# ETH_SWITCH.net
KiCad netlist of a schematic drawn in Altium Designer
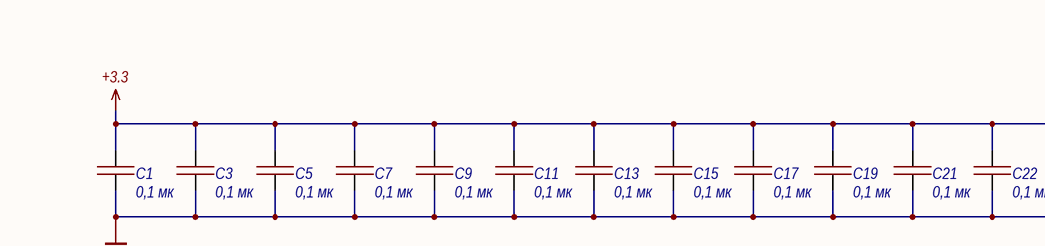
[diagram p0: ETH_SWITCH.SchDoc, top left]
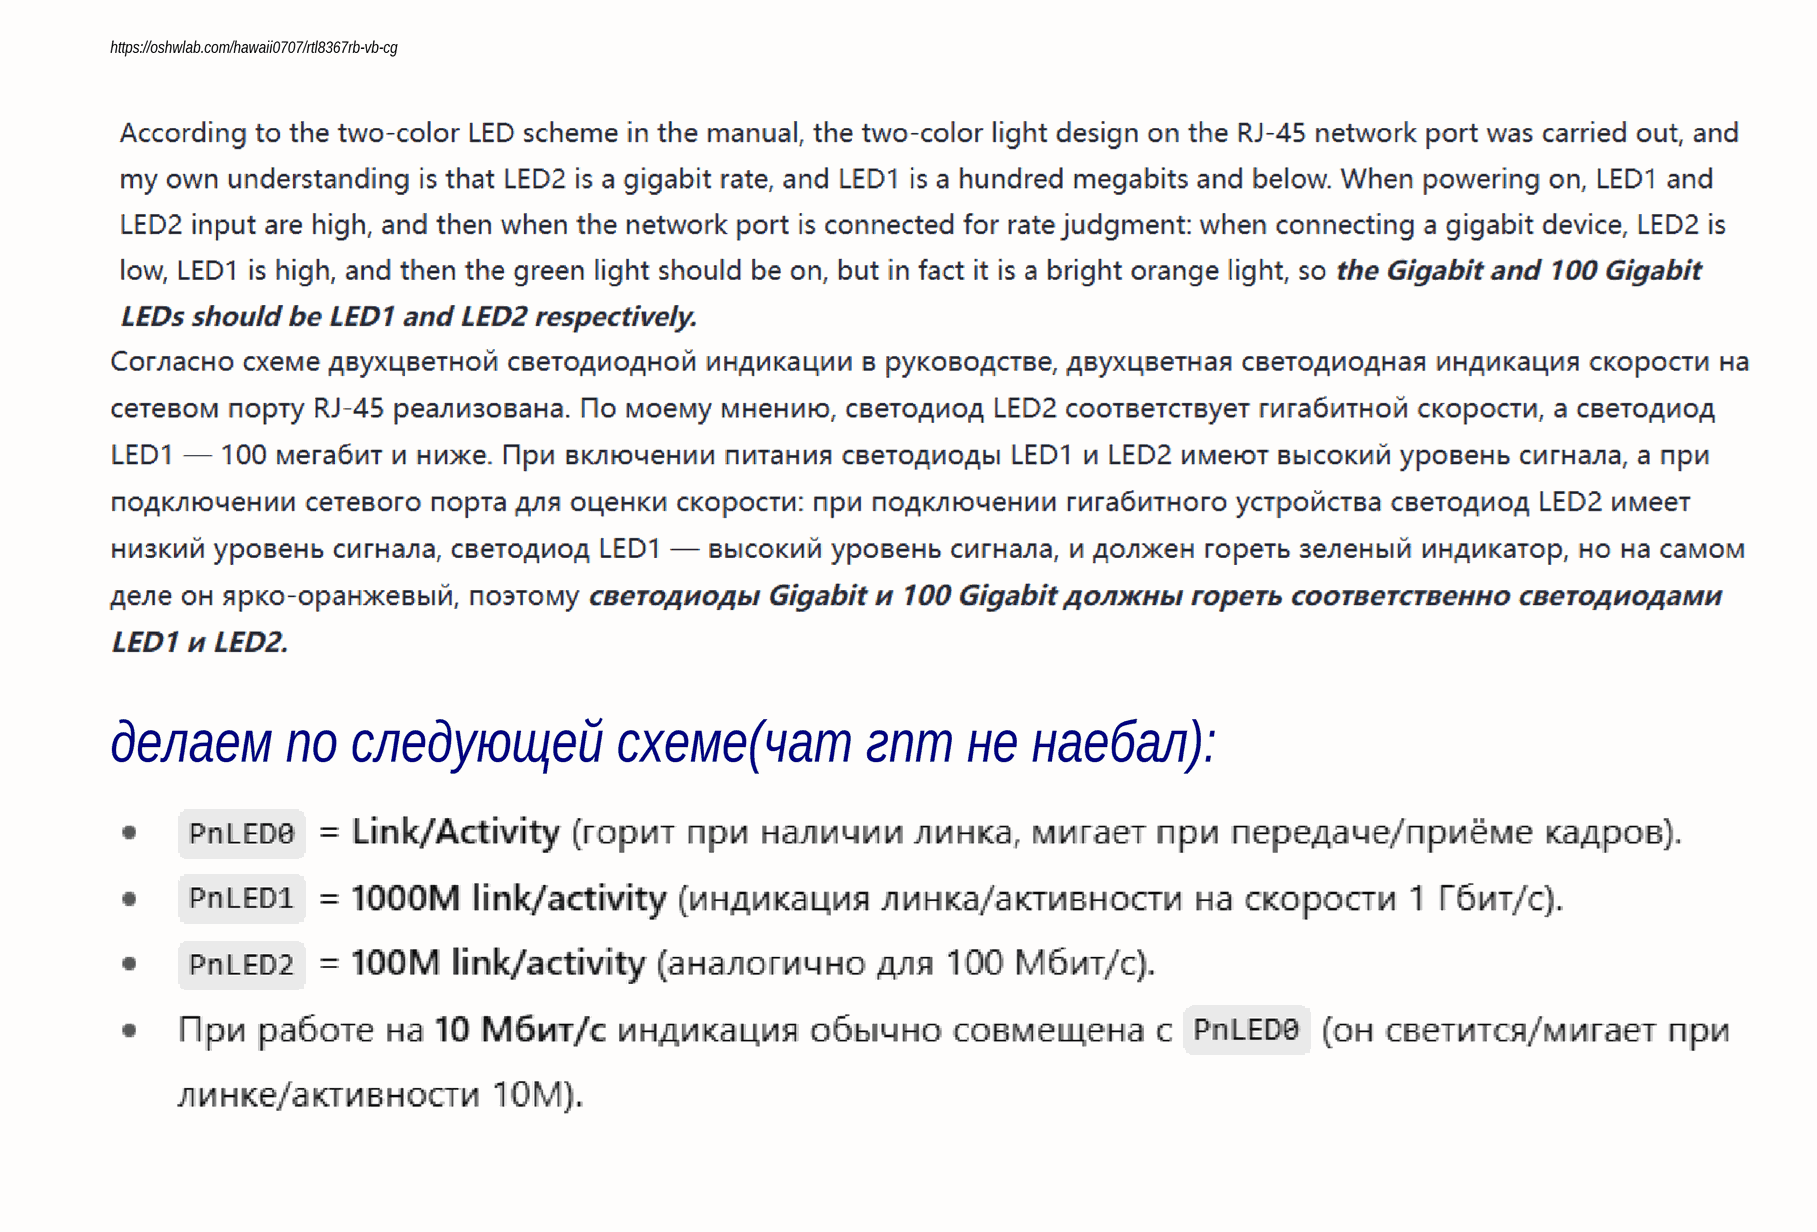
[diagram p1: ETH_SWITCH.SchDoc, top right]
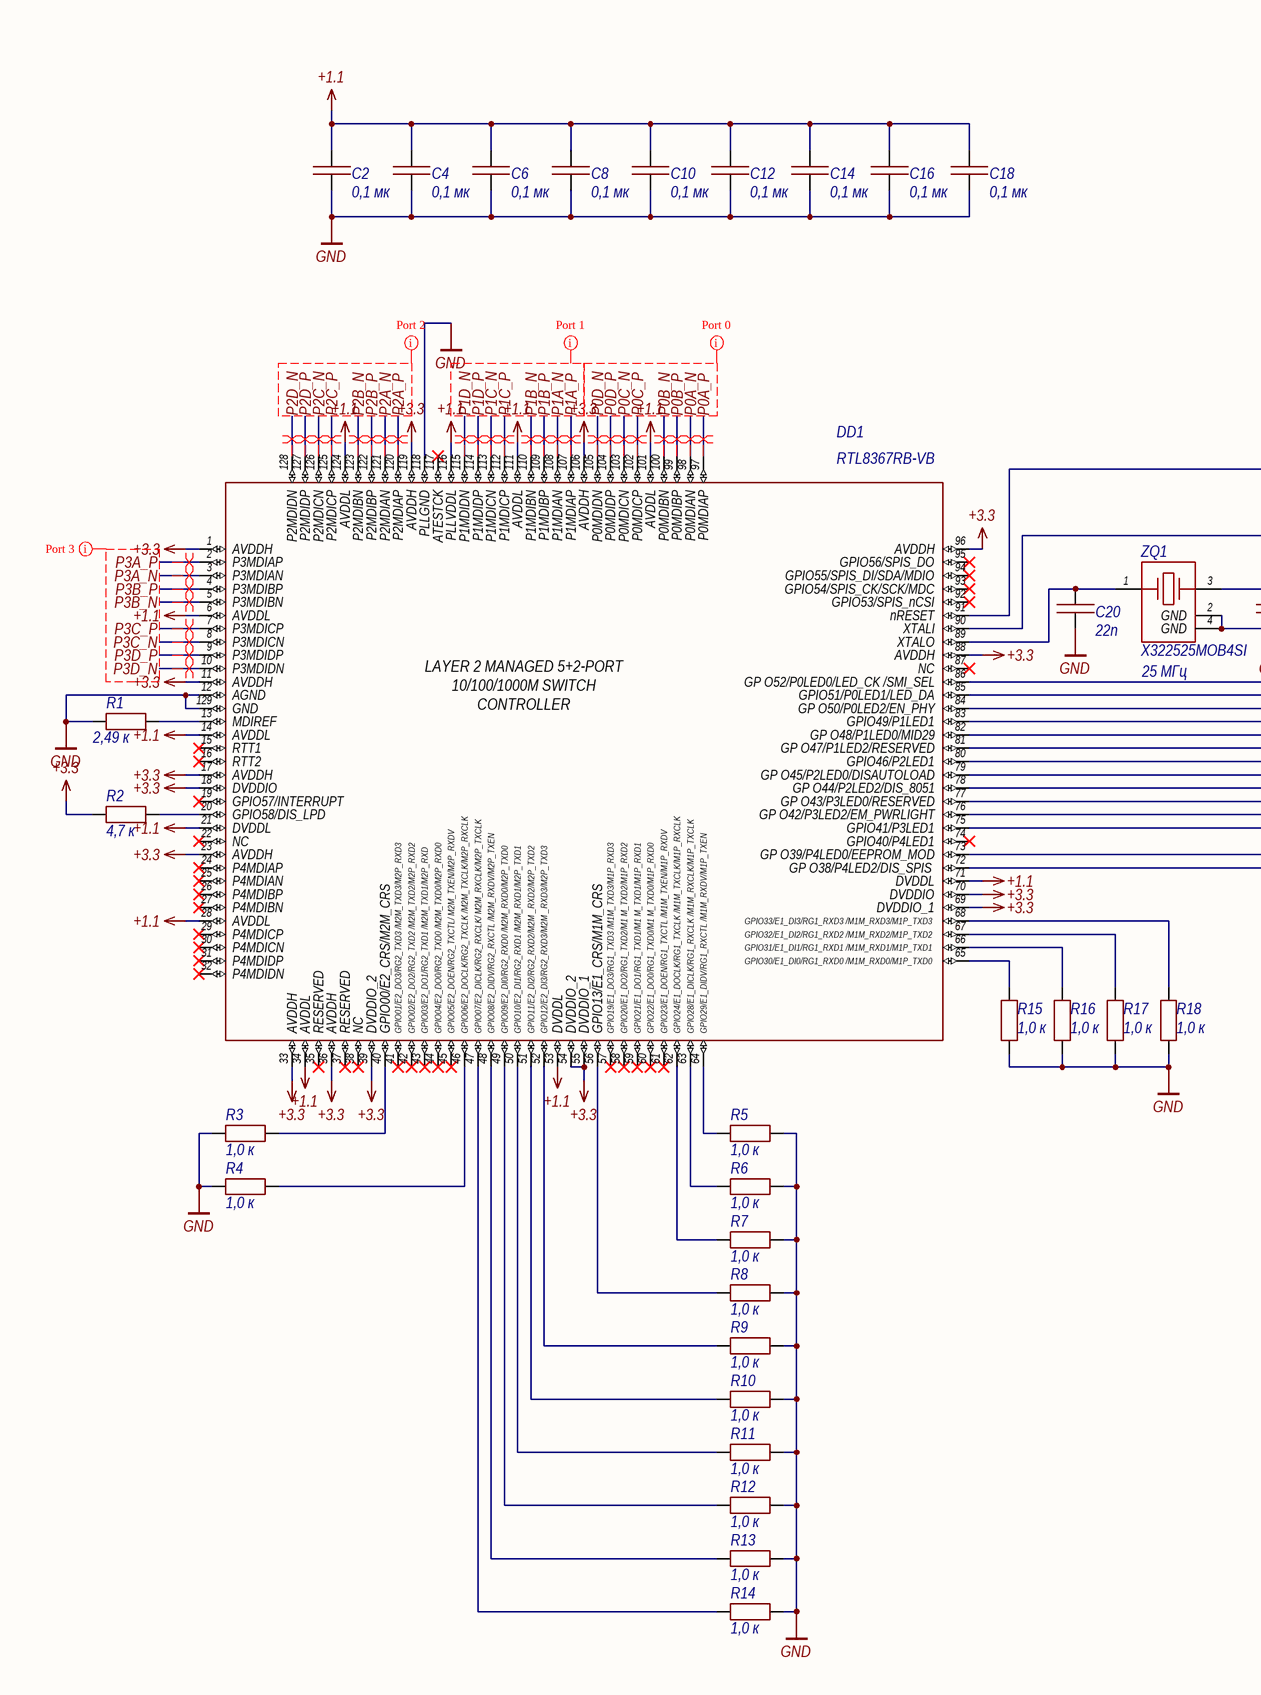
[diagram p2: ETH_SWITCH.SchDoc, bottom left]
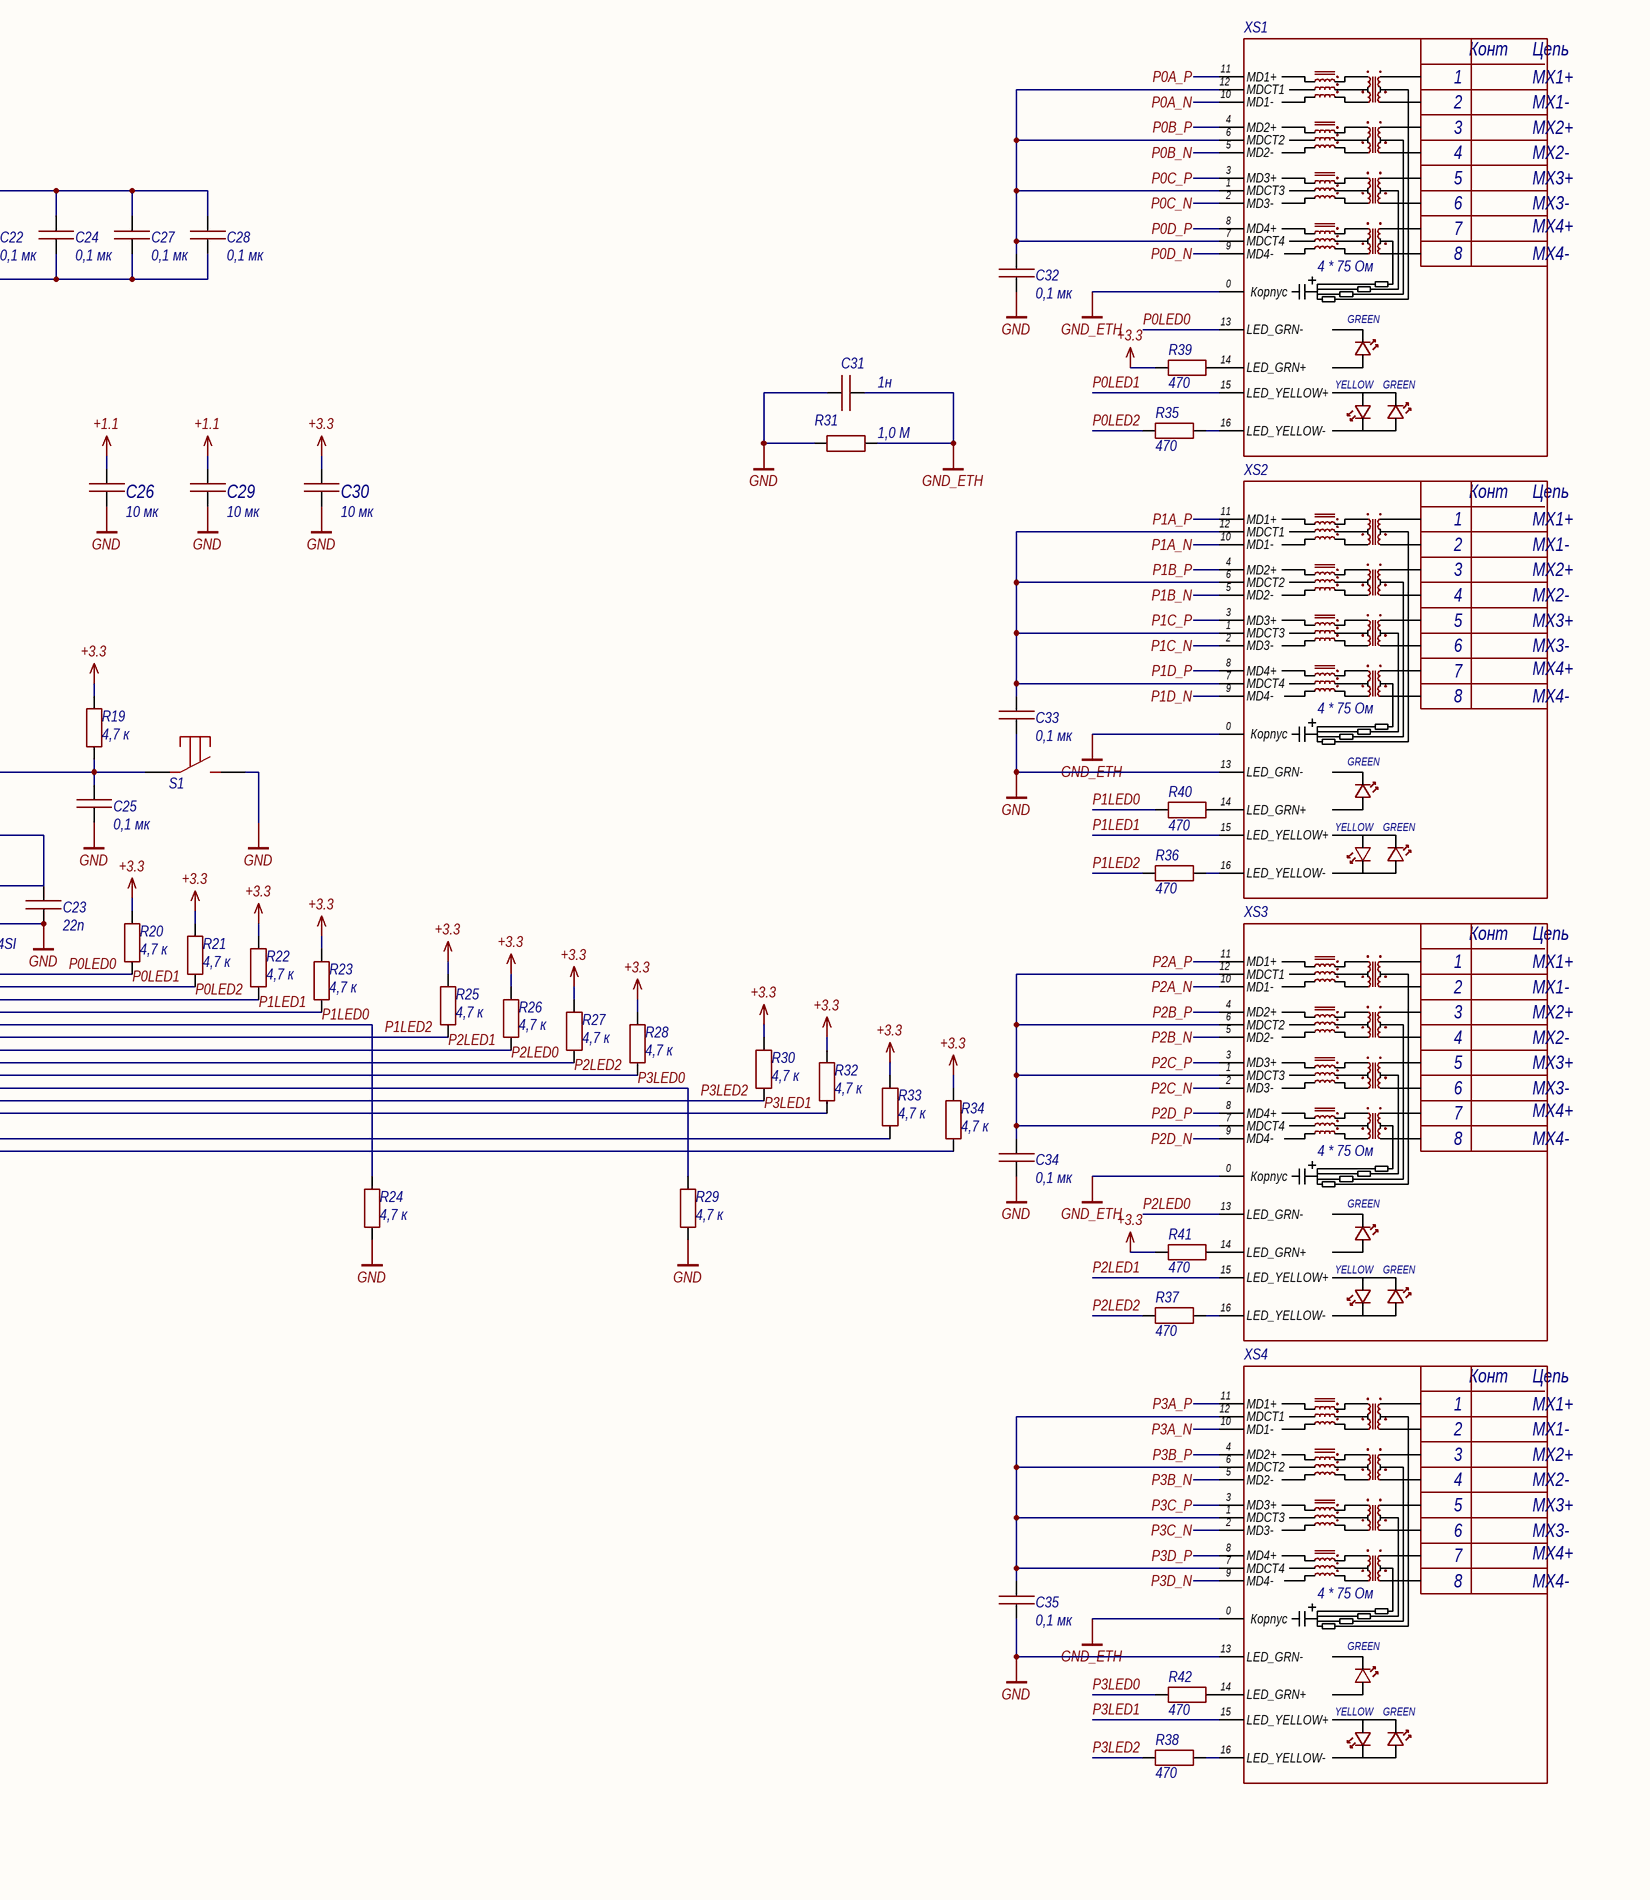
[diagram p3: ETH_SWITCH.SchDoc, bottom right]

(export (version "E")
  (design (tool "Eeschema 10.0.6"))
  (components
    (comp (ref "C1")
      (value "0,1 мк")
      (footprint "0402C")
      (description "Конденсатор 0402C ёмкостью 0,1 мк 10%, 16 В, X7R")
      (fields
        (field (name "PART NUMBER") "Capacitor_0,1u_10_16V_X7R_0603C")
        (field (name "TOLERANCE") "10%")
        (field (name "АВТОР") "rreali")
      )
      (libsource (lib "Hydrolib") (part "Capacitor"))
    )
    (comp (ref "C2")
      (value "0,1 мк")
      (footprint "0402C")
      (description "Конденсатор 0402C ёмкостью 0,1 мк 10%, 16 В, X7R")
      (fields
        (field (name "PART NUMBER") "Capacitor_0,1u_10_16V_X7R_0603C")
        (field (name "TOLERANCE") "10%")
        (field (name "АВТОР") "rreali")
      )
      (libsource (lib "Hydrolib") (part "Capacitor"))
    )
    (comp (ref "C3")
      (value "0,1 мк")
      (footprint "0402C")
      (description "Конденсатор 0402C ёмкостью 0,1 мк 10%, 16 В, X7R")
      (fields
        (field (name "PART NUMBER") "Capacitor_0,1u_10_16V_X7R_0603C")
        (field (name "TOLERANCE") "10%")
        (field (name "АВТОР") "rreali")
      )
      (libsource (lib "Hydrolib") (part "Capacitor"))
    )
    (comp (ref "C4")
      (value "0,1 мк")
      (footprint "0402C")
      (description "Конденсатор 0402C ёмкостью 0,1 мк 10%, 16 В, X7R")
      (fields
        (field (name "PART NUMBER") "Capacitor_0,1u_10_16V_X7R_0603C")
        (field (name "TOLERANCE") "10%")
        (field (name "АВТОР") "rreali")
      )
      (libsource (lib "Hydrolib") (part "Capacitor"))
    )
    (comp (ref "C5")
      (value "0,1 мк")
      (footprint "0402C")
      (description "Конденсатор 0402C ёмкостью 0,1 мк 10%, 16 В, X7R")
      (fields
        (field (name "PART NUMBER") "Capacitor_0,1u_10_16V_X7R_0603C")
        (field (name "TOLERANCE") "10%")
        (field (name "АВТОР") "rreali")
      )
      (libsource (lib "Hydrolib") (part "Capacitor"))
    )
    (comp (ref "C6")
      (value "0,1 мк")
      (footprint "0402C")
      (description "Конденсатор 0402C ёмкостью 0,1 мк 10%, 16 В, X7R")
      (fields
        (field (name "PART NUMBER") "Capacitor_0,1u_10_16V_X7R_0603C")
        (field (name "TOLERANCE") "10%")
        (field (name "АВТОР") "rreali")
      )
      (libsource (lib "Hydrolib") (part "Capacitor"))
    )
    (comp (ref "C7")
      (value "0,1 мк")
      (footprint "0402C")
      (description "Конденсатор 0402C ёмкостью 0,1 мк 10%, 16 В, X7R")
      (fields
        (field (name "PART NUMBER") "Capacitor_0,1u_10_16V_X7R_0603C")
        (field (name "TOLERANCE") "10%")
        (field (name "АВТОР") "rreali")
      )
      (libsource (lib "Hydrolib") (part "Capacitor"))
    )
    (comp (ref "C8")
      (value "0,1 мк")
      (footprint "0402C")
      (description "Конденсатор 0402C ёмкостью 0,1 мк 10%, 16 В, X7R")
      (fields
        (field (name "PART NUMBER") "Capacitor_0,1u_10_16V_X7R_0603C")
        (field (name "TOLERANCE") "10%")
        (field (name "АВТОР") "rreali")
      )
      (libsource (lib "Hydrolib") (part "Capacitor"))
    )
    (comp (ref "C9")
      (value "0,1 мк")
      (footprint "0402C")
      (description "Конденсатор 0402C ёмкостью 0,1 мк 10%, 16 В, X7R")
      (fields
        (field (name "PART NUMBER") "Capacitor_0,1u_10_16V_X7R_0603C")
        (field (name "TOLERANCE") "10%")
        (field (name "АВТОР") "rreali")
      )
      (libsource (lib "Hydrolib") (part "Capacitor"))
    )
    (comp (ref "C10")
      (value "0,1 мк")
      (footprint "0402C")
      (description "Конденсатор 0402C ёмкостью 0,1 мк 10%, 16 В, X7R")
      (fields
        (field (name "PART NUMBER") "Capacitor_0,1u_10_16V_X7R_0603C")
        (field (name "TOLERANCE") "10%")
        (field (name "АВТОР") "rreali")
      )
      (libsource (lib "Hydrolib") (part "Capacitor"))
    )
    (comp (ref "C11")
      (value "0,1 мк")
      (footprint "0402C")
      (description "Конденсатор 0402C ёмкостью 0,1 мк 10%, 16 В, X7R")
      (fields
        (field (name "PART NUMBER") "Capacitor_0,1u_10_16V_X7R_0603C")
        (field (name "TOLERANCE") "10%")
        (field (name "АВТОР") "rreali")
      )
      (libsource (lib "Hydrolib") (part "Capacitor"))
    )
    (comp (ref "C12")
      (value "0,1 мк")
      (footprint "0402C")
      (description "Конденсатор 0402C ёмкостью 0,1 мк 10%, 16 В, X7R")
      (fields
        (field (name "PART NUMBER") "Capacitor_0,1u_10_16V_X7R_0603C")
        (field (name "TOLERANCE") "10%")
        (field (name "АВТОР") "rreali")
      )
      (libsource (lib "Hydrolib") (part "Capacitor"))
    )
    (comp (ref "C13")
      (value "0,1 мк")
      (footprint "0402C")
      (description "Конденсатор 0402C ёмкостью 0,1 мк 10%, 16 В, X7R")
      (fields
        (field (name "PART NUMBER") "Capacitor_0,1u_10_16V_X7R_0603C")
        (field (name "TOLERANCE") "10%")
        (field (name "АВТОР") "rreali")
      )
      (libsource (lib "Hydrolib") (part "Capacitor"))
    )
    (comp (ref "C14")
      (value "0,1 мк")
      (footprint "0402C")
      (description "Конденсатор 0402C ёмкостью 0,1 мк 10%, 16 В, X7R")
      (fields
        (field (name "PART NUMBER") "Capacitor_0,1u_10_16V_X7R_0603C")
        (field (name "TOLERANCE") "10%")
        (field (name "АВТОР") "rreali")
      )
      (libsource (lib "Hydrolib") (part "Capacitor"))
    )
    (comp (ref "C15")
      (value "0,1 мк")
      (footprint "0402C")
      (description "Конденсатор 0402C ёмкостью 0,1 мк 10%, 16 В, X7R")
      (fields
        (field (name "PART NUMBER") "Capacitor_0,1u_10_16V_X7R_0603C")
        (field (name "TOLERANCE") "10%")
        (field (name "АВТОР") "rreali")
      )
      (libsource (lib "Hydrolib") (part "Capacitor"))
    )
    (comp (ref "C16")
      (value "0,1 мк")
      (footprint "0402C")
      (description "Конденсатор 0402C ёмкостью 0,1 мк 10%, 16 В, X7R")
      (fields
        (field (name "PART NUMBER") "Capacitor_0,1u_10_16V_X7R_0603C")
        (field (name "TOLERANCE") "10%")
        (field (name "АВТОР") "rreali")
      )
      (libsource (lib "Hydrolib") (part "Capacitor"))
    )
    (comp (ref "C17")
      (value "0,1 мк")
      (footprint "0402C")
      (description "Конденсатор 0402C ёмкостью 0,1 мк 10%, 16 В, X7R")
      (fields
        (field (name "PART NUMBER") "Capacitor_0,1u_10_16V_X7R_0603C")
        (field (name "TOLERANCE") "10%")
        (field (name "АВТОР") "rreali")
      )
      (libsource (lib "Hydrolib") (part "Capacitor"))
    )
    (comp (ref "C18")
      (value "0,1 мк")
      (footprint "0402C")
      (description "Конденсатор 0402C ёмкостью 0,1 мк 10%, 16 В, X7R")
      (fields
        (field (name "PART NUMBER") "Capacitor_0,1u_10_16V_X7R_0603C")
        (field (name "TOLERANCE") "10%")
        (field (name "АВТОР") "rreali")
      )
      (libsource (lib "Hydrolib") (part "Capacitor"))
    )
    (comp (ref "C19")
      (value "0,1 мк")
      (footprint "0402C")
      (description "Конденсатор 0402C ёмкостью 0,1 мк 10%, 16 В, X7R")
      (fields
        (field (name "PART NUMBER") "Capacitor_0,1u_10_16V_X7R_0603C")
        (field (name "TOLERANCE") "10%")
        (field (name "АВТОР") "rreali")
      )
      (libsource (lib "Hydrolib") (part "Capacitor"))
    )
    (comp (ref "C20")
      (value "22п")
      (footprint "0603C")
      (description "Конденсатор 0603C ёмкостью 22п 5%, 50 В, NP0")
      (fields (field (name "PART NUMBER") "GRM1885C1H220J") (field (name "TOLERANCE") "5%"))
      (libsource (lib "Hydrolib") (part "Capacitor"))
    )
    (comp (ref "C21")
      (value "0,1 мк")
      (footprint "0402C")
      (description "Конденсатор 0402C ёмкостью 0,1 мк 10%, 16 В, X7R")
      (fields
        (field (name "PART NUMBER") "Capacitor_0,1u_10_16V_X7R_0603C")
        (field (name "TOLERANCE") "10%")
        (field (name "АВТОР") "rreali")
      )
      (libsource (lib "Hydrolib") (part "Capacitor"))
    )
    (comp (ref "C22")
      (value "0,1 мк")
      (footprint "0402C")
      (description "Конденсатор 0402C ёмкостью 0,1 мк 10%, 16 В, X7R")
      (fields
        (field (name "PART NUMBER") "Capacitor_0,1u_10_16V_X7R_0603C")
        (field (name "TOLERANCE") "10%")
        (field (name "АВТОР") "rreali")
      )
      (libsource (lib "Hydrolib") (part "Capacitor"))
    )
    (comp (ref "C23")
      (value "22п")
      (footprint "0603C")
      (description "Конденсатор 0603C ёмкостью 22п 5%, 50 В, NP0")
      (fields (field (name "PART NUMBER") "GRM1885C1H220J") (field (name "TOLERANCE") "5%"))
      (libsource (lib "Hydrolib") (part "Capacitor"))
    )
    (comp (ref "C24")
      (value "0,1 мк")
      (footprint "0402C")
      (description "Конденсатор 0402C ёмкостью 0,1 мк 10%, 16 В, X7R")
      (fields
        (field (name "PART NUMBER") "Capacitor_0,1u_10_16V_X7R_0603C")
        (field (name "TOLERANCE") "10%")
        (field (name "АВТОР") "rreali")
      )
      (libsource (lib "Hydrolib") (part "Capacitor"))
    )
    (comp (ref "C25")
      (value "0,1 мк")
      (footprint "0603C")
      (description "Конденсатор 0603C ёмкостью 0,1 мк 10%, 50 В, X7R")
      (fields (field (name "PART NUMBER") "Capacitor_0,1u_10_50V_X7R_0603C") (field (name "TOLERANCE") "10%"))
      (libsource (lib "Hydrolib") (part "Capacitor"))
    )
    (comp (ref "C26")
      (value "10 мк")
      (footprint "1210C")
      (description "Конденсатор")
      (fields (field (name "PART NUMBER") "Capacitor_10u_10_35V_X7R_1210C") (field (name "TOLERANCE") "0,1"))
      (libsource (lib "Hydrolib") (part "Capacitor"))
    )
    (comp (ref "C27")
      (value "0,1 мк")
      (footprint "0402C")
      (description "Конденсатор 0402C ёмкостью 0,1 мк 10%, 16 В, X7R")
      (fields
        (field (name "PART NUMBER") "Capacitor_0,1u_10_16V_X7R_0603C")
        (field (name "TOLERANCE") "10%")
        (field (name "АВТОР") "rreali")
      )
      (libsource (lib "Hydrolib") (part "Capacitor"))
    )
    (comp (ref "C28")
      (value "0,1 мк")
      (footprint "0402C")
      (description "Конденсатор 0402C ёмкостью 0,1 мк 10%, 16 В, X7R")
      (fields
        (field (name "PART NUMBER") "Capacitor_0,1u_10_16V_X7R_0603C")
        (field (name "TOLERANCE") "10%")
        (field (name "АВТОР") "rreali")
      )
      (libsource (lib "Hydrolib") (part "Capacitor"))
    )
    (comp (ref "C29")
      (value "10 мк")
      (footprint "1210C")
      (description "Конденсатор")
      (fields (field (name "PART NUMBER") "Capacitor_10u_10_35V_X7R_1210C") (field (name "TOLERANCE") "0,1"))
      (libsource (lib "Hydrolib") (part "Capacitor"))
    )
    (comp (ref "C30")
      (value "10 мк")
      (footprint "1210C")
      (description "Конденсатор")
      (fields (field (name "PART NUMBER") "Capacitor_10u_10_35V_X7R_1210C") (field (name "TOLERANCE") "0,1"))
      (libsource (lib "Hydrolib") (part "Capacitor"))
    )
    (comp (ref "C31")
      (value "1н")
      (footprint "1210C")
      (description "Конденсатор 1210C ёмкостью 1н 10%, 1000 В, X7R")
      (fields (field (name "PART NUMBER") "Capacitor_1n_10_1000V_X7R_1206C") (field (name "TOLERANCE") "10%"))
      (libsource (lib "Hydrolib") (part "Capacitor"))
    )
    (comp (ref "C32")
      (value "0,1 мк")
      (footprint "0603C")
      (description "Конденсатор 0603C ёмкостью 0,1 мк 10%, 50 В, X7R")
      (fields (field (name "PART NUMBER") "Capacitor_0,1u_10_50V_X7R_0603C") (field (name "TOLERANCE") "10%"))
      (libsource (lib "Hydrolib") (part "Capacitor"))
    )
    (comp (ref "C33")
      (value "0,1 мк")
      (footprint "0603C")
      (description "Конденсатор 0603C ёмкостью 0,1 мк 10%, 50 В, X7R")
      (fields (field (name "PART NUMBER") "Capacitor_0,1u_10_50V_X7R_0603C") (field (name "TOLERANCE") "10%"))
      (libsource (lib "Hydrolib") (part "Capacitor"))
    )
    (comp (ref "C34")
      (value "0,1 мк")
      (footprint "0603C")
      (description "Конденсатор 0603C ёмкостью 0,1 мк 10%, 50 В, X7R")
      (fields (field (name "PART NUMBER") "Capacitor_0,1u_10_50V_X7R_0603C") (field (name "TOLERANCE") "10%"))
      (libsource (lib "Hydrolib") (part "Capacitor"))
    )
    (comp (ref "C35")
      (value "0,1 мк")
      (footprint "0603C")
      (description "Конденсатор 0603C ёмкостью 0,1 мк 10%, 50 В, X7R")
      (fields (field (name "PART NUMBER") "Capacitor_0,1u_10_50V_X7R_0603C") (field (name "TOLERANCE") "10%"))
      (libsource (lib "Hydrolib") (part "Capacitor"))
    )
    (comp (ref "DD1")
      (value "RTL8367RB-VB")
      (footprint "LQFP128_14x14_exposed_pad")
      (description "Управляемый коммутатор второго уровня на 5+2 порта 10/100/1000M")
      (fields (field (name "MF") "Realtek") (field (name "MP") "RTL8367RB"))
      (libsource (lib "Hydrolib") (part "RTL8367RB-VB"))
    )
    (comp (ref "R1")
      (value "2,49 к")
      (footprint "0603R")
      (description "0.1Вт 0603 2.49 кОм, 1%, Чип резистор")
      (fields (field (name "PART NUMBER") "RC0603FR-072K49L") (field (name "TOLERANCE") "1%"))
      (libsource (lib "") (part "Resistor_2"))
    )
    (comp (ref "R2")
      (value "4,7 к")
      (footprint "0402R")
      (description "Резистор номиналом 4,7 кОм 1%")
      (fields
        (field (name "PART NUMBER") "Resistor_4.7k_1_0402")
        (field (name "TOLERANCE") "1%")
        (field (name "АВТОР") "rreali")
      )
      (libsource (lib "") (part "Resistor_2"))
    )
    (comp (ref "R3")
      (value "1,0 к")
      (footprint "0402R")
      (description "Резистор номиналом 1,0 кОм 1%")
      (fields
        (field (name "PART NUMBER") "Resistor_1.0k_1_0402")
        (field (name "TOLERANCE") "1%")
        (field (name "АВТОР") "rreali")
      )
      (libsource (lib "") (part "Resistor_1"))
    )
    (comp (ref "R4")
      (value "1,0 к")
      (footprint "0402R")
      (description "Резистор номиналом 1,0 кОм 1%")
      (fields
        (field (name "PART NUMBER") "Resistor_1.0k_1_0402")
        (field (name "TOLERANCE") "1%")
        (field (name "АВТОР") "rreali")
      )
      (libsource (lib "") (part "Resistor_1"))
    )
    (comp (ref "R5")
      (value "1,0 к")
      (footprint "0402R")
      (description "Резистор номиналом 1,0 кОм 1%")
      (fields
        (field (name "PART NUMBER") "Resistor_1.0k_1_0402")
        (field (name "TOLERANCE") "1%")
        (field (name "АВТОР") "rreali")
      )
      (libsource (lib "") (part "Resistor_1"))
    )
    (comp (ref "R6")
      (value "1,0 к")
      (footprint "0402R")
      (description "Резистор номиналом 1,0 кОм 1%")
      (fields
        (field (name "PART NUMBER") "Resistor_1.0k_1_0402")
        (field (name "TOLERANCE") "1%")
        (field (name "АВТОР") "rreali")
      )
      (libsource (lib "") (part "Resistor_1"))
    )
    (comp (ref "R7")
      (value "1,0 к")
      (footprint "0402R")
      (description "Резистор номиналом 1,0 кОм 1%")
      (fields
        (field (name "PART NUMBER") "Resistor_1.0k_1_0402")
        (field (name "TOLERANCE") "1%")
        (field (name "АВТОР") "rreali")
      )
      (libsource (lib "") (part "Resistor_1"))
    )
    (comp (ref "R8")
      (value "1,0 к")
      (footprint "0402R")
      (description "Резистор номиналом 1,0 кОм 1%")
      (fields
        (field (name "PART NUMBER") "Resistor_1.0k_1_0402")
        (field (name "TOLERANCE") "1%")
        (field (name "АВТОР") "rreali")
      )
      (libsource (lib "") (part "Resistor_1"))
    )
    (comp (ref "R9")
      (value "1,0 к")
      (footprint "0402R")
      (description "Резистор номиналом 1,0 кОм 1%")
      (fields
        (field (name "PART NUMBER") "Resistor_1.0k_1_0402")
        (field (name "TOLERANCE") "1%")
        (field (name "АВТОР") "rreali")
      )
      (libsource (lib "") (part "Resistor_1"))
    )
    (comp (ref "R10")
      (value "1,0 к")
      (footprint "0402R")
      (description "Резистор номиналом 1,0 кОм 1%")
      (fields
        (field (name "PART NUMBER") "Resistor_1.0k_1_0402")
        (field (name "TOLERANCE") "1%")
        (field (name "АВТОР") "rreali")
      )
      (libsource (lib "") (part "Resistor_1"))
    )
    (comp (ref "R11")
      (value "1,0 к")
      (footprint "0402R")
      (description "Резистор номиналом 1,0 кОм 1%")
      (fields
        (field (name "PART NUMBER") "Resistor_1.0k_1_0402")
        (field (name "TOLERANCE") "1%")
        (field (name "АВТОР") "rreali")
      )
      (libsource (lib "") (part "Resistor_1"))
    )
    (comp (ref "R12")
      (value "1,0 к")
      (footprint "0402R")
      (description "Резистор номиналом 1,0 кОм 1%")
      (fields
        (field (name "PART NUMBER") "Resistor_1.0k_1_0402")
        (field (name "TOLERANCE") "1%")
        (field (name "АВТОР") "rreali")
      )
      (libsource (lib "") (part "Resistor_1"))
    )
    (comp (ref "R13")
      (value "1,0 к")
      (footprint "0402R")
      (description "Резистор номиналом 1,0 кОм 1%")
      (fields
        (field (name "PART NUMBER") "Resistor_1.0k_1_0402")
        (field (name "TOLERANCE") "1%")
        (field (name "АВТОР") "rreali")
      )
      (libsource (lib "") (part "Resistor_1"))
    )
    (comp (ref "R14")
      (value "1,0 к")
      (footprint "0402R")
      (description "Резистор номиналом 1,0 кОм 1%")
      (fields
        (field (name "PART NUMBER") "Resistor_1.0k_1_0402")
        (field (name "TOLERANCE") "1%")
        (field (name "АВТОР") "rreali")
      )
      (libsource (lib "") (part "Resistor_1"))
    )
    (comp (ref "R15")
      (value "1,0 к")
      (footprint "0402R")
      (description "Резистор номиналом 1,0 кОм 1%")
      (fields
        (field (name "PART NUMBER") "Resistor_1.0k_1_0402")
        (field (name "TOLERANCE") "1%")
        (field (name "АВТОР") "rreali")
      )
      (libsource (lib "Hydrolib") (part "Resistor"))
    )
    (comp (ref "R16")
      (value "1,0 к")
      (footprint "0402R")
      (description "Резистор номиналом 1,0 кОм 1%")
      (fields
        (field (name "PART NUMBER") "Resistor_1.0k_1_0402")
        (field (name "TOLERANCE") "1%")
        (field (name "АВТОР") "rreali")
      )
      (libsource (lib "Hydrolib") (part "Resistor"))
    )
    (comp (ref "R17")
      (value "1,0 к")
      (footprint "0402R")
      (description "Резистор номиналом 1,0 кОм 1%")
      (fields
        (field (name "PART NUMBER") "Resistor_1.0k_1_0402")
        (field (name "TOLERANCE") "1%")
        (field (name "АВТОР") "rreali")
      )
      (libsource (lib "Hydrolib") (part "Resistor"))
    )
    (comp (ref "R18")
      (value "1,0 к")
      (footprint "0402R")
      (description "Резистор номиналом 1,0 кОм 1%")
      (fields
        (field (name "PART NUMBER") "Resistor_1.0k_1_0402")
        (field (name "TOLERANCE") "1%")
        (field (name "АВТОР") "rreali")
      )
      (libsource (lib "Hydrolib") (part "Resistor"))
    )
    (comp (ref "R19")
      (value "4,7 к")
      (footprint "0402R")
      (description "Резистор номиналом 4,7 кОм 1%")
      (fields
        (field (name "PART NUMBER") "Resistor_4.7k_1_0402")
        (field (name "TOLERANCE") "1%")
        (field (name "АВТОР") "rreali")
      )
      (libsource (lib "Hydrolib") (part "Resistor"))
    )
    (comp (ref "R20")
      (value "4,7 к")
      (footprint "0402R")
      (description "Резистор номиналом 4,7 кОм 1%")
      (fields
        (field (name "PART NUMBER") "Resistor_4.7k_1_0402")
        (field (name "TOLERANCE") "1%")
        (field (name "АВТОР") "rreali")
      )
      (libsource (lib "Hydrolib") (part "Resistor"))
    )
    (comp (ref "R21")
      (value "4,7 к")
      (footprint "0402R")
      (description "Резистор номиналом 4,7 кОм 1%")
      (fields
        (field (name "PART NUMBER") "Resistor_4.7k_1_0402")
        (field (name "TOLERANCE") "1%")
        (field (name "АВТОР") "rreali")
      )
      (libsource (lib "Hydrolib") (part "Resistor"))
    )
    (comp (ref "R22")
      (value "4,7 к")
      (footprint "0402R")
      (description "Резистор номиналом 4,7 кОм 1%")
      (fields
        (field (name "PART NUMBER") "Resistor_4.7k_1_0402")
        (field (name "TOLERANCE") "1%")
        (field (name "АВТОР") "rreali")
      )
      (libsource (lib "Hydrolib") (part "Resistor"))
    )
    (comp (ref "R23")
      (value "4,7 к")
      (footprint "0402R")
      (description "Резистор номиналом 4,7 кОм 1%")
      (fields
        (field (name "PART NUMBER") "Resistor_4.7k_1_0402")
        (field (name "TOLERANCE") "1%")
        (field (name "АВТОР") "rreali")
      )
      (libsource (lib "Hydrolib") (part "Resistor"))
    )
    (comp (ref "R24")
      (value "4,7 к")
      (footprint "0402R")
      (description "Резистор номиналом 4,7 кОм 1%")
      (fields
        (field (name "PART NUMBER") "Resistor_4.7k_1_0402")
        (field (name "TOLERANCE") "1%")
        (field (name "АВТОР") "rreali")
      )
      (libsource (lib "Hydrolib") (part "Resistor"))
    )
    (comp (ref "R25")
      (value "4,7 к")
      (footprint "0402R")
      (description "Резистор номиналом 4,7 кОм 1%")
      (fields
        (field (name "PART NUMBER") "Resistor_4.7k_1_0402")
        (field (name "TOLERANCE") "1%")
        (field (name "АВТОР") "rreali")
      )
      (libsource (lib "Hydrolib") (part "Resistor"))
    )
    (comp (ref "R26")
      (value "4,7 к")
      (footprint "0402R")
      (description "Резистор номиналом 4,7 кОм 1%")
      (fields
        (field (name "PART NUMBER") "Resistor_4.7k_1_0402")
        (field (name "TOLERANCE") "1%")
        (field (name "АВТОР") "rreali")
      )
      (libsource (lib "Hydrolib") (part "Resistor"))
    )
    (comp (ref "R27")
      (value "4,7 к")
      (footprint "0402R")
      (description "Резистор номиналом 4,7 кОм 1%")
      (fields
        (field (name "PART NUMBER") "Resistor_4.7k_1_0402")
        (field (name "TOLERANCE") "1%")
        (field (name "АВТОР") "rreali")
      )
      (libsource (lib "Hydrolib") (part "Resistor"))
    )
    (comp (ref "R28")
      (value "4,7 к")
      (footprint "0402R")
      (description "Резистор номиналом 4,7 кОм 1%")
      (fields
        (field (name "PART NUMBER") "Resistor_4.7k_1_0402")
        (field (name "TOLERANCE") "1%")
        (field (name "АВТОР") "rreali")
      )
      (libsource (lib "Hydrolib") (part "Resistor"))
    )
    (comp (ref "R29")
      (value "4,7 к")
      (footprint "0402R")
      (description "Резистор номиналом 4,7 кОм 1%")
      (fields
        (field (name "PART NUMBER") "Resistor_4.7k_1_0402")
        (field (name "TOLERANCE") "1%")
        (field (name "АВТОР") "rreali")
      )
      (libsource (lib "Hydrolib") (part "Resistor"))
    )
    (comp (ref "R30")
      (value "4,7 к")
      (footprint "0402R")
      (description "Резистор номиналом 4,7 кОм 1%")
      (fields
        (field (name "PART NUMBER") "Resistor_4.7k_1_0402")
        (field (name "TOLERANCE") "1%")
        (field (name "АВТОР") "rreali")
      )
      (libsource (lib "Hydrolib") (part "Resistor"))
    )
    (comp (ref "R31")
      (value "1,0 М")
      (footprint "0603R")
      (description "Резистор номиналом 1,0 МОм 1%")
      (fields (field (name "PART NUMBER") "Resistor_1.0M_1_0603") (field (name "TOLERANCE") "1%"))
      (libsource (lib "") (part "Resistor_2"))
    )
    (comp (ref "R32")
      (value "4,7 к")
      (footprint "0402R")
      (description "Резистор номиналом 4,7 кОм 1%")
      (fields
        (field (name "PART NUMBER") "Resistor_4.7k_1_0402")
        (field (name "TOLERANCE") "1%")
        (field (name "АВТОР") "rreali")
      )
      (libsource (lib "Hydrolib") (part "Resistor"))
    )
    (comp (ref "R33")
      (value "4,7 к")
      (footprint "0402R")
      (description "Резистор номиналом 4,7 кОм 1%")
      (fields
        (field (name "PART NUMBER") "Resistor_4.7k_1_0402")
        (field (name "TOLERANCE") "1%")
        (field (name "АВТОР") "rreali")
      )
      (libsource (lib "Hydrolib") (part "Resistor"))
    )
    (comp (ref "R34")
      (value "4,7 к")
      (footprint "0402R")
      (description "Резистор номиналом 4,7 кОм 1%")
      (fields
        (field (name "PART NUMBER") "Resistor_4.7k_1_0402")
        (field (name "TOLERANCE") "1%")
        (field (name "АВТОР") "rreali")
      )
      (libsource (lib "Hydrolib") (part "Resistor"))
    )
    (comp (ref "R35")
      (value "470")
      (footprint "0402R")
      (description "Резистор номиналом 470 Ом 1%")
      (fields
        (field (name "PART NUMBER") "Resistor_470_1_0402")
        (field (name "TOLERANCE") "1%")
        (field (name "АВТОР") "rreali")
      )
      (libsource (lib "") (part "Resistor_2"))
    )
    (comp (ref "R36")
      (value "470")
      (footprint "0402R")
      (description "Резистор номиналом 470 Ом 1%")
      (fields
        (field (name "PART NUMBER") "Resistor_470_1_0402")
        (field (name "TOLERANCE") "1%")
        (field (name "АВТОР") "rreali")
      )
      (libsource (lib "") (part "Resistor_2"))
    )
    (comp (ref "R37")
      (value "470")
      (footprint "0402R")
      (description "Резистор номиналом 470 Ом 1%")
      (fields
        (field (name "PART NUMBER") "Resistor_470_1_0402")
        (field (name "TOLERANCE") "1%")
        (field (name "АВТОР") "rreali")
      )
      (libsource (lib "") (part "Resistor_2"))
    )
    (comp (ref "R38")
      (value "470")
      (footprint "0402R")
      (description "Резистор номиналом 470 Ом 1%")
      (fields
        (field (name "PART NUMBER") "Resistor_470_1_0402")
        (field (name "TOLERANCE") "1%")
        (field (name "АВТОР") "rreali")
      )
      (libsource (lib "") (part "Resistor_2"))
    )
    (comp (ref "R39")
      (value "470")
      (footprint "0402R")
      (description "Резистор номиналом 470 Ом 1%")
      (fields
        (field (name "PART NUMBER") "Resistor_470_1_0402")
        (field (name "TOLERANCE") "1%")
        (field (name "АВТОР") "rreali")
      )
      (libsource (lib "") (part "Resistor_2"))
    )
    (comp (ref "R40")
      (value "470")
      (footprint "0402R")
      (description "Резистор номиналом 470 Ом 1%")
      (fields
        (field (name "PART NUMBER") "Resistor_470_1_0402")
        (field (name "TOLERANCE") "1%")
        (field (name "АВТОР") "rreali")
      )
      (libsource (lib "") (part "Resistor_2"))
    )
    (comp (ref "R41")
      (value "470")
      (footprint "0402R")
      (description "Резистор номиналом 470 Ом 1%")
      (fields
        (field (name "PART NUMBER") "Resistor_470_1_0402")
        (field (name "TOLERANCE") "1%")
        (field (name "АВТОР") "rreali")
      )
      (libsource (lib "") (part "Resistor_2"))
    )
    (comp (ref "R42")
      (value "470")
      (footprint "0402R")
      (description "Резистор номиналом 470 Ом 1%")
      (fields
        (field (name "PART NUMBER") "Resistor_470_1_0402")
        (field (name "TOLERANCE") "1%")
        (field (name "АВТОР") "rreali")
      )
      (libsource (lib "") (part "Resistor_2"))
    )
    (comp (ref "S1")
      (value "Tact_button")
      (footprint "Button_SMD_6x6")
      (description "Тактовая кнопка")
      (libsource (lib "Hydrolib") (part "Tact_button"))
    )
    (comp (ref "XS1")
      (value "~")
      (footprint "JK00136NL")
      (description "Модульный разъем (с трансформатором) Cat5/6, RJ45, Гнездо,  1 порт")
      (fields (field (name "MP") "JK0-0136NL") (field (name "MF") "Pulse Electronics"))
      (libsource (lib "Hydrolib") (part "JK0-0136NL"))
    )
    (comp (ref "XS2")
      (value "~")
      (footprint "JK00136NL")
      (description "Модульный разъем (с трансформатором) Cat5/6, RJ45, Гнездо,  1 порт")
      (fields (field (name "MP") "JK0-0136NL") (field (name "MF") "Pulse Electronics"))
      (libsource (lib "Hydrolib") (part "JK0-0136NL"))
    )
    (comp (ref "XS3")
      (value "~")
      (footprint "JK00136NL")
      (description "Модульный разъем (с трансформатором) Cat5/6, RJ45, Гнездо,  1 порт")
      (fields (field (name "MP") "JK0-0136NL") (field (name "MF") "Pulse Electronics"))
      (libsource (lib "Hydrolib") (part "JK0-0136NL"))
    )
    (comp (ref "XS4")
      (value "~")
      (footprint "JK00136NL")
      (description "Модульный разъем (с трансформатором) Cat5/6, RJ45, Гнездо,  1 порт")
      (fields (field (name "MP") "JK0-0136NL") (field (name "MF") "Pulse Electronics"))
      (libsource (lib "Hydrolib") (part "JK0-0136NL"))
    )
    (comp (ref "ZQ1")
      (value "X322525MOB4SI")
      (footprint "X322525MOB4SI")
      (description "Кварцевый резонатор SMD 25 МГц ±10ppm SMD-3225_4P")
      (fields (field (name "ALTIUM_VALUE") "25 МГц"))
      (libsource (lib "Hydrolib") (part "XTAL_1-3_GND"))
    )
  )
  (nets
    (net (code "1") (name "+1.1") (class "Default")
      (node (ref "C10") (pin "2") (pinfunction "2_2") (pintype "passive"))
      (node (ref "C12") (pin "2") (pinfunction "2_2") (pintype "passive"))
      (node (ref "C14") (pin "2") (pinfunction "2_2") (pintype "passive"))
      (node (ref "C16") (pin "2") (pinfunction "2_2") (pintype "passive"))
      (node (ref "C18") (pin "2") (pinfunction "2_2") (pintype "passive"))
      (node (ref "C2") (pin "2") (pinfunction "2_2") (pintype "passive"))
      (node (ref "C26") (pin "2") (pinfunction "2_2") (pintype "passive"))
      (node (ref "C29") (pin "2") (pinfunction "2_2") (pintype "passive"))
      (node (ref "C4") (pin "2") (pinfunction "2_2") (pintype "passive"))
      (node (ref "C6") (pin "2") (pinfunction "2_2") (pintype "passive"))
      (node (ref "C8") (pin "2") (pinfunction "2_2") (pintype "passive"))
      (node (ref "DD1") (pin "101") (pinfunction "AVDDL_101") (pintype "bidirectional"))
      (node (ref "DD1") (pin "111") (pinfunction "AVDDL_111") (pintype "bidirectional"))
      (node (ref "DD1") (pin "116") (pinfunction "PLLVDDL_116") (pintype "bidirectional"))
      (node (ref "DD1") (pin "124") (pinfunction "AVDDL_124") (pintype "bidirectional"))
      (node (ref "DD1") (pin "14") (pinfunction "AVDDL_14") (pintype "bidirectional"))
      (node (ref "DD1") (pin "21") (pinfunction "DVDDL_21") (pintype "bidirectional"))
      (node (ref "DD1") (pin "28") (pinfunction "AVDDL_28") (pintype "bidirectional"))
      (node (ref "DD1") (pin "34") (pinfunction "AVDDL_34") (pintype "bidirectional"))
      (node (ref "DD1") (pin "53") (pinfunction "DVDDL_53") (pintype "bidirectional"))
      (node (ref "DD1") (pin "6") (pinfunction "AVDDL_6") (pintype "bidirectional"))
      (node (ref "DD1") (pin "71") (pinfunction "DVDDL_71") (pintype "bidirectional"))
    )
    (net (code "2") (name "+3.3") (class "Default")
      (node (ref "C1") (pin "2") (pinfunction "2_2") (pintype "passive"))
      (node (ref "C11") (pin "2") (pinfunction "2_2") (pintype "passive"))
      (node (ref "C13") (pin "2") (pinfunction "2_2") (pintype "passive"))
      (node (ref "C15") (pin "2") (pinfunction "2_2") (pintype "passive"))
      (node (ref "C17") (pin "2") (pinfunction "2_2") (pintype "passive"))
      (node (ref "C19") (pin "2") (pinfunction "2_2") (pintype "passive"))
      (node (ref "C21") (pin "2") (pinfunction "2_2") (pintype "passive"))
      (node (ref "C22") (pin "2") (pinfunction "2_2") (pintype "passive"))
      (node (ref "C24") (pin "2") (pinfunction "2_2") (pintype "passive"))
      (node (ref "C27") (pin "2") (pinfunction "2_2") (pintype "passive"))
      (node (ref "C28") (pin "2") (pinfunction "2_2") (pintype "passive"))
      (node (ref "C3") (pin "2") (pinfunction "2_2") (pintype "passive"))
      (node (ref "C30") (pin "2") (pinfunction "2_2") (pintype "passive"))
      (node (ref "C5") (pin "2") (pinfunction "2_2") (pintype "passive"))
      (node (ref "C7") (pin "2") (pinfunction "2_2") (pintype "passive"))
      (node (ref "C9") (pin "2") (pinfunction "2_2") (pintype "passive"))
      (node (ref "DD1") (pin "1") (pinfunction "AVDDH_1") (pintype "bidirectional"))
      (node (ref "DD1") (pin "106") (pinfunction "AVDDH_106") (pintype "bidirectional"))
      (node (ref "DD1") (pin "11") (pinfunction "AVDDH_11") (pintype "bidirectional"))
      (node (ref "DD1") (pin "119") (pinfunction "AVDDH_119") (pintype "bidirectional"))
      (node (ref "DD1") (pin "17") (pinfunction "AVDDH_17") (pintype "bidirectional"))
      (node (ref "DD1") (pin "18") (pinfunction "DVDDIO_18") (pintype "bidirectional"))
      (node (ref "DD1") (pin "23") (pinfunction "AVDDH_23") (pintype "bidirectional"))
      (node (ref "DD1") (pin "33") (pinfunction "AVDDH_33") (pintype "bidirectional"))
      (node (ref "DD1") (pin "36") (pinfunction "AVDDH_36") (pintype "bidirectional"))
      (node (ref "DD1") (pin "39") (pinfunction "DVDDIO_2_39") (pintype "bidirectional"))
      (node (ref "DD1") (pin "54") (pinfunction "DVDDIO_2_54") (pintype "bidirectional"))
      (node (ref "DD1") (pin "55") (pinfunction "DVDDIO_1_55") (pintype "bidirectional"))
      (node (ref "DD1") (pin "69") (pinfunction "DVDDIO_1_69") (pintype "bidirectional"))
      (node (ref "DD1") (pin "70") (pinfunction "DVDDIO_70") (pintype "bidirectional"))
      (node (ref "DD1") (pin "88") (pinfunction "AVDDH_88") (pintype "bidirectional"))
      (node (ref "DD1") (pin "96") (pinfunction "AVDDH_96") (pintype "bidirectional"))
      (node (ref "R19") (pin "2") (pinfunction "2_2") (pintype "passive"))
      (node (ref "R2") (pin "1") (pinfunction "1_1") (pintype "passive"))
      (node (ref "R20") (pin "2") (pinfunction "2_2") (pintype "passive"))
      (node (ref "R21") (pin "2") (pinfunction "2_2") (pintype "passive"))
      (node (ref "R22") (pin "2") (pinfunction "2_2") (pintype "passive"))
      (node (ref "R23") (pin "2") (pinfunction "2_2") (pintype "passive"))
      (node (ref "R25") (pin "2") (pinfunction "2_2") (pintype "passive"))
      (node (ref "R26") (pin "2") (pinfunction "2_2") (pintype "passive"))
      (node (ref "R27") (pin "2") (pinfunction "2_2") (pintype "passive"))
      (node (ref "R28") (pin "2") (pinfunction "2_2") (pintype "passive"))
      (node (ref "R30") (pin "2") (pinfunction "2_2") (pintype "passive"))
      (node (ref "R32") (pin "2") (pinfunction "2_2") (pintype "passive"))
      (node (ref "R33") (pin "2") (pinfunction "2_2") (pintype "passive"))
      (node (ref "R34") (pin "2") (pinfunction "2_2") (pintype "passive"))
      (node (ref "R39") (pin "1") (pinfunction "1_1") (pintype "passive"))
      (node (ref "R41") (pin "1") (pinfunction "1_1") (pintype "passive"))
    )
    (net (code "3") (name "/P0A_N") (class "Default")
      (node (ref "DD1") (pin "98") (pinfunction "P0MDIAN_98") (pintype "bidirectional"))
      (node (ref "XS1") (pin "10") (pinfunction "MD1-_10") (pintype "passive"))
    )
    (net (code "4") (name "/P0A_P") (class "Default")
      (node (ref "DD1") (pin "97") (pinfunction "P0MDIAP_97") (pintype "bidirectional"))
      (node (ref "XS1") (pin "11") (pinfunction "MD1+_11") (pintype "passive"))
    )
    (net (code "5") (name "/P0B_N") (class "Default")
      (node (ref "DD1") (pin "100") (pinfunction "P0MDIBN_100") (pintype "bidirectional"))
      (node (ref "XS1") (pin "5") (pinfunction "MD2-_5") (pintype "passive"))
    )
    (net (code "6") (name "/P0B_P") (class "Default")
      (node (ref "DD1") (pin "99") (pinfunction "P0MDIBP_99") (pintype "bidirectional"))
      (node (ref "XS1") (pin "4") (pinfunction "MD2+_4") (pintype "passive"))
    )
    (net (code "7") (name "/P0C_N") (class "Default")
      (node (ref "DD1") (pin "103") (pinfunction "P0MDICN_103") (pintype "bidirectional"))
      (node (ref "XS1") (pin "2") (pinfunction "MD3-_2") (pintype "passive"))
    )
    (net (code "8") (name "/P0C_P") (class "Default")
      (node (ref "DD1") (pin "102") (pinfunction "P0MDICP_102") (pintype "bidirectional"))
      (node (ref "XS1") (pin "3") (pinfunction "MD3+_3") (pintype "passive"))
    )
    (net (code "9") (name "/P0D_N") (class "Default")
      (node (ref "DD1") (pin "105") (pinfunction "P0MDIDN_105") (pintype "bidirectional"))
      (node (ref "XS1") (pin "9") (pinfunction "MD4-_9") (pintype "passive"))
    )
    (net (code "10") (name "/P0D_P") (class "Default")
      (node (ref "DD1") (pin "104") (pinfunction "P0MDIDP_104") (pintype "bidirectional"))
      (node (ref "XS1") (pin "8") (pinfunction "MD4+_8") (pintype "passive"))
    )
    (net (code "11") (name "/P0LED0") (class "Default")
      (node (ref "DD1") (pin "86") (pinfunction "GP_O52/P0LED0/LED_CK_/SMI_SEL_86") (pintype "bidirectional"))
      (node (ref "R20") (pin "1") (pinfunction "1_1") (pintype "passive"))
      (node (ref "XS1") (pin "13") (pinfunction "LED_GRN-_13") (pintype "passive"))
    )
    (net (code "12") (name "/P0LED1") (class "Default")
      (node (ref "DD1") (pin "85") (pinfunction "GPIO51/P0LED1/LED_DA_85") (pintype "bidirectional"))
      (node (ref "R21") (pin "1") (pinfunction "1_1") (pintype "passive"))
      (node (ref "XS1") (pin "15") (pinfunction "LED_YELLOW+_15") (pintype "passive"))
    )
    (net (code "13") (name "/P0LED2") (class "Default")
      (node (ref "DD1") (pin "84") (pinfunction "GP_O50/P0LED2/EN_PHY_84") (pintype "bidirectional"))
      (node (ref "R22") (pin "1") (pinfunction "1_1") (pintype "passive"))
      (node (ref "R35") (pin "1") (pinfunction "1_1") (pintype "passive"))
    )
    (net (code "14") (name "/P1A_N") (class "Default")
      (node (ref "DD1") (pin "108") (pinfunction "P1MDIAN_108") (pintype "bidirectional"))
      (node (ref "XS2") (pin "10") (pinfunction "MD1-_10") (pintype "passive"))
    )
    (net (code "15") (name "/P1A_P") (class "Default")
      (node (ref "DD1") (pin "107") (pinfunction "P1MDIAP_107") (pintype "bidirectional"))
      (node (ref "XS2") (pin "11") (pinfunction "MD1+_11") (pintype "passive"))
    )
    (net (code "16") (name "/P1B_N") (class "Default")
      (node (ref "DD1") (pin "110") (pinfunction "P1MDIBN_110") (pintype "bidirectional"))
      (node (ref "XS2") (pin "5") (pinfunction "MD2-_5") (pintype "passive"))
    )
    (net (code "17") (name "/P1B_P") (class "Default")
      (node (ref "DD1") (pin "109") (pinfunction "P1MDIBP_109") (pintype "bidirectional"))
      (node (ref "XS2") (pin "4") (pinfunction "MD2+_4") (pintype "passive"))
    )
    (net (code "18") (name "/P1C_N") (class "Default")
      (node (ref "DD1") (pin "113") (pinfunction "P1MDICN_113") (pintype "bidirectional"))
      (node (ref "XS2") (pin "2") (pinfunction "MD3-_2") (pintype "passive"))
    )
    (net (code "19") (name "/P1C_P") (class "Default")
      (node (ref "DD1") (pin "112") (pinfunction "P1MDICP_112") (pintype "bidirectional"))
      (node (ref "XS2") (pin "3") (pinfunction "MD3+_3") (pintype "passive"))
    )
    (net (code "20") (name "/P1D_N") (class "Default")
      (node (ref "DD1") (pin "115") (pinfunction "P1MDIDN_115") (pintype "bidirectional"))
      (node (ref "XS2") (pin "9") (pinfunction "MD4-_9") (pintype "passive"))
    )
    (net (code "21") (name "/P1D_P") (class "Default")
      (node (ref "DD1") (pin "114") (pinfunction "P1MDIDP_114") (pintype "bidirectional"))
      (node (ref "XS2") (pin "8") (pinfunction "MD4+_8") (pintype "passive"))
    )
    (net (code "22") (name "/P1LED0") (class "Default")
      (node (ref "DD1") (pin "82") (pinfunction "GP_O48/P1LED0/MID29_82") (pintype "bidirectional"))
      (node (ref "R24") (pin "2") (pinfunction "2_2") (pintype "passive"))
      (node (ref "R40") (pin "1") (pinfunction "1_1") (pintype "passive"))
    )
    (net (code "23") (name "/P1LED1") (class "Default")
      (node (ref "DD1") (pin "83") (pinfunction "GPIO49/P1LED1_83") (pintype "bidirectional"))
      (node (ref "R23") (pin "1") (pinfunction "1_1") (pintype "passive"))
      (node (ref "XS2") (pin "15") (pinfunction "LED_YELLOW+_15") (pintype "passive"))
    )
    (net (code "24") (name "/P1LED2") (class "Default")
      (node (ref "DD1") (pin "81") (pinfunction "GP_O47/P1LED2/RESERVED_81") (pintype "bidirectional"))
      (node (ref "R25") (pin "1") (pinfunction "1_1") (pintype "passive"))
      (node (ref "R36") (pin "1") (pinfunction "1_1") (pintype "passive"))
    )
    (net (code "25") (name "/P2A_N") (class "Default")
      (node (ref "DD1") (pin "121") (pinfunction "P2MDIAN_121") (pintype "bidirectional"))
      (node (ref "XS3") (pin "10") (pinfunction "MD1-_10") (pintype "passive"))
    )
    (net (code "26") (name "/P2A_P") (class "Default")
      (node (ref "DD1") (pin "120") (pinfunction "P2MDIAP_120") (pintype "bidirectional"))
      (node (ref "XS3") (pin "11") (pinfunction "MD1+_11") (pintype "passive"))
    )
    (net (code "27") (name "/P2B_N") (class "Default")
      (node (ref "DD1") (pin "123") (pinfunction "P2MDIBN_123") (pintype "bidirectional"))
      (node (ref "XS3") (pin "5") (pinfunction "MD2-_5") (pintype "passive"))
    )
    (net (code "28") (name "/P2B_P") (class "Default")
      (node (ref "DD1") (pin "122") (pinfunction "P2MDIBP_122") (pintype "bidirectional"))
      (node (ref "XS3") (pin "4") (pinfunction "MD2+_4") (pintype "passive"))
    )
    (net (code "29") (name "/P2C_N") (class "Default")
      (node (ref "DD1") (pin "126") (pinfunction "P2MDICN_126") (pintype "bidirectional"))
      (node (ref "XS3") (pin "2") (pinfunction "MD3-_2") (pintype "passive"))
    )
    (net (code "30") (name "/P2C_P") (class "Default")
      (node (ref "DD1") (pin "125") (pinfunction "P2MDICP_125") (pintype "bidirectional"))
      (node (ref "XS3") (pin "3") (pinfunction "MD3+_3") (pintype "passive"))
    )
    (net (code "31") (name "/P2D_N") (class "Default")
      (node (ref "DD1") (pin "128") (pinfunction "P2MDIDN_128") (pintype "bidirectional"))
      (node (ref "XS3") (pin "9") (pinfunction "MD4-_9") (pintype "passive"))
    )
    (net (code "32") (name "/P2D_P") (class "Default")
      (node (ref "DD1") (pin "127") (pinfunction "P2MDIDP_127") (pintype "bidirectional"))
      (node (ref "XS3") (pin "8") (pinfunction "MD4+_8") (pintype "passive"))
    )
    (net (code "33") (name "/P2LED0") (class "Default")
      (node (ref "DD1") (pin "79") (pinfunction "GP_O45/P2LED0/DISAUTOLOAD_79") (pintype "bidirectional"))
      (node (ref "R27") (pin "1") (pinfunction "1_1") (pintype "passive"))
      (node (ref "XS3") (pin "13") (pinfunction "LED_GRN-_13") (pintype "passive"))
    )
    (net (code "34") (name "/P2LED1") (class "Default")
      (node (ref "DD1") (pin "80") (pinfunction "GPIO46/P2LED1_80") (pintype "bidirectional"))
      (node (ref "R26") (pin "1") (pinfunction "1_1") (pintype "passive"))
      (node (ref "XS3") (pin "15") (pinfunction "LED_YELLOW+_15") (pintype "passive"))
    )
    (net (code "35") (name "/P2LED2") (class "Default")
      (node (ref "DD1") (pin "78") (pinfunction "GP_O44/P2LED2/DIS_8051_78") (pintype "bidirectional"))
      (node (ref "R28") (pin "1") (pinfunction "1_1") (pintype "passive"))
      (node (ref "R37") (pin "1") (pinfunction "1_1") (pintype "passive"))
    )
    (net (code "36") (name "/P3A_N") (class "Default")
      (node (ref "DD1") (pin "3") (pinfunction "P3MDIAN_3") (pintype "bidirectional"))
      (node (ref "XS4") (pin "10") (pinfunction "MD1-_10") (pintype "passive"))
    )
    (net (code "37") (name "/P3A_P") (class "Default")
      (node (ref "DD1") (pin "2") (pinfunction "P3MDIAP_2") (pintype "bidirectional"))
      (node (ref "XS4") (pin "11") (pinfunction "MD1+_11") (pintype "passive"))
    )
    (net (code "38") (name "/P3B_N") (class "Default")
      (node (ref "DD1") (pin "5") (pinfunction "P3MDIBN_5") (pintype "bidirectional"))
      (node (ref "XS4") (pin "5") (pinfunction "MD2-_5") (pintype "passive"))
    )
    (net (code "39") (name "/P3B_P") (class "Default")
      (node (ref "DD1") (pin "4") (pinfunction "P3MDIBP_4") (pintype "bidirectional"))
      (node (ref "XS4") (pin "4") (pinfunction "MD2+_4") (pintype "passive"))
    )
    (net (code "40") (name "/P3C_N") (class "Default")
      (node (ref "DD1") (pin "8") (pinfunction "P3MDICN_8") (pintype "bidirectional"))
      (node (ref "XS4") (pin "2") (pinfunction "MD3-_2") (pintype "passive"))
    )
    (net (code "41") (name "/P3C_P") (class "Default")
      (node (ref "DD1") (pin "7") (pinfunction "P3MDICP_7") (pintype "bidirectional"))
      (node (ref "XS4") (pin "3") (pinfunction "MD3+_3") (pintype "passive"))
    )
    (net (code "42") (name "/P3D_N") (class "Default")
      (node (ref "DD1") (pin "10") (pinfunction "P3MDIDN_10") (pintype "bidirectional"))
      (node (ref "XS4") (pin "9") (pinfunction "MD4-_9") (pintype "passive"))
    )
    (net (code "43") (name "/P3D_P") (class "Default")
      (node (ref "DD1") (pin "9") (pinfunction "P3MDIDP_9") (pintype "bidirectional"))
      (node (ref "XS4") (pin "8") (pinfunction "MD4+_8") (pintype "passive"))
    )
    (net (code "44") (name "/P3LED0") (class "Default")
      (node (ref "DD1") (pin "77") (pinfunction "GP_O43/P3LED0/RESERVED_77") (pintype "bidirectional"))
      (node (ref "R29") (pin "2") (pinfunction "2_2") (pintype "passive"))
      (node (ref "R42") (pin "1") (pinfunction "1_1") (pintype "passive"))
    )
    (net (code "45") (name "/P3LED1") (class "Default")
      (node (ref "DD1") (pin "75") (pinfunction "GPIO41/P3LED1_75") (pintype "bidirectional"))
      (node (ref "R32") (pin "1") (pinfunction "1_1") (pintype "passive"))
      (node (ref "XS4") (pin "15") (pinfunction "LED_YELLOW+_15") (pintype "passive"))
    )
    (net (code "46") (name "/P3LED2") (class "Default")
      (node (ref "DD1") (pin "76") (pinfunction "GP_O42/P3LED2/EM_PWRLIGHT_76") (pintype "bidirectional"))
      (node (ref "R30") (pin "1") (pinfunction "1_1") (pintype "passive"))
      (node (ref "R38") (pin "1") (pinfunction "1_1") (pintype "passive"))
    )
    (net (code "47") (name "GND") (class "Default")
      (node (ref "C1") (pin "1") (pinfunction "1_1") (pintype "passive"))
      (node (ref "C10") (pin "1") (pinfunction "1_1") (pintype "passive"))
      (node (ref "C11") (pin "1") (pinfunction "1_1") (pintype "passive"))
      (node (ref "C12") (pin "1") (pinfunction "1_1") (pintype "passive"))
      (node (ref "C13") (pin "1") (pinfunction "1_1") (pintype "passive"))
      (node (ref "C14") (pin "1") (pinfunction "1_1") (pintype "passive"))
      (node (ref "C15") (pin "1") (pinfunction "1_1") (pintype "passive"))
      (node (ref "C16") (pin "1") (pinfunction "1_1") (pintype "passive"))
      (node (ref "C17") (pin "1") (pinfunction "1_1") (pintype "passive"))
      (node (ref "C18") (pin "1") (pinfunction "1_1") (pintype "passive"))
      (node (ref "C19") (pin "1") (pinfunction "1_1") (pintype "passive"))
      (node (ref "C2") (pin "1") (pinfunction "1_1") (pintype "passive"))
      (node (ref "C20") (pin "1") (pinfunction "1_1") (pintype "passive"))
      (node (ref "C21") (pin "1") (pinfunction "1_1") (pintype "passive"))
      (node (ref "C22") (pin "1") (pinfunction "1_1") (pintype "passive"))
      (node (ref "C23") (pin "2") (pinfunction "2_2") (pintype "passive"))
      (node (ref "C24") (pin "1") (pinfunction "1_1") (pintype "passive"))
      (node (ref "C25") (pin "1") (pinfunction "1_1") (pintype "passive"))
      (node (ref "C26") (pin "1") (pinfunction "1_1") (pintype "passive"))
      (node (ref "C27") (pin "1") (pinfunction "1_1") (pintype "passive"))
      (node (ref "C28") (pin "1") (pinfunction "1_1") (pintype "passive"))
      (node (ref "C29") (pin "1") (pinfunction "1_1") (pintype "passive"))
      (node (ref "C3") (pin "1") (pinfunction "1_1") (pintype "passive"))
      (node (ref "C30") (pin "1") (pinfunction "1_1") (pintype "passive"))
      (node (ref "C31") (pin "1") (pinfunction "1_1") (pintype "passive"))
      (node (ref "C32") (pin "2") (pinfunction "2_2") (pintype "passive"))
      (node (ref "C33") (pin "2") (pinfunction "2_2") (pintype "passive"))
      (node (ref "C34") (pin "2") (pinfunction "2_2") (pintype "passive"))
      (node (ref "C35") (pin "2") (pinfunction "2_2") (pintype "passive"))
      (node (ref "C4") (pin "1") (pinfunction "1_1") (pintype "passive"))
      (node (ref "C5") (pin "1") (pinfunction "1_1") (pintype "passive"))
      (node (ref "C6") (pin "1") (pinfunction "1_1") (pintype "passive"))
      (node (ref "C7") (pin "1") (pinfunction "1_1") (pintype "passive"))
      (node (ref "C8") (pin "1") (pinfunction "1_1") (pintype "passive"))
      (node (ref "C9") (pin "1") (pinfunction "1_1") (pintype "passive"))
      (node (ref "DD1") (pin "118") (pinfunction "PLLGND_118") (pintype "bidirectional"))
      (node (ref "DD1") (pin "12") (pinfunction "AGND_12") (pintype "bidirectional"))
      (node (ref "DD1") (pin "129") (pinfunction "GND_129") (pintype "bidirectional"))
      (node (ref "R1") (pin "1") (pinfunction "1_1") (pintype "passive"))
      (node (ref "R10") (pin "1") (pinfunction "1_1") (pintype "passive"))
      (node (ref "R11") (pin "1") (pinfunction "1_1") (pintype "passive"))
      (node (ref "R12") (pin "1") (pinfunction "1_1") (pintype "passive"))
      (node (ref "R13") (pin "1") (pinfunction "1_1") (pintype "passive"))
      (node (ref "R14") (pin "1") (pinfunction "1_1") (pintype "passive"))
      (node (ref "R15") (pin "1") (pinfunction "1_1") (pintype "passive"))
      (node (ref "R16") (pin "1") (pinfunction "1_1") (pintype "passive"))
      (node (ref "R17") (pin "1") (pinfunction "1_1") (pintype "passive"))
      (node (ref "R18") (pin "1") (pinfunction "1_1") (pintype "passive"))
      (node (ref "R24") (pin "1") (pinfunction "1_1") (pintype "passive"))
      (node (ref "R29") (pin "1") (pinfunction "1_1") (pintype "passive"))
      (node (ref "R3") (pin "2") (pinfunction "2_2") (pintype "passive"))
      (node (ref "R31") (pin "1") (pinfunction "1_1") (pintype "passive"))
      (node (ref "R4") (pin "2") (pinfunction "2_2") (pintype "passive"))
      (node (ref "R5") (pin "1") (pinfunction "1_1") (pintype "passive"))
      (node (ref "R6") (pin "1") (pinfunction "1_1") (pintype "passive"))
      (node (ref "R7") (pin "1") (pinfunction "1_1") (pintype "passive"))
      (node (ref "R8") (pin "1") (pinfunction "1_1") (pintype "passive"))
      (node (ref "R9") (pin "1") (pinfunction "1_1") (pintype "passive"))
      (node (ref "S1") (pin "2") (pinfunction "2_2") (pintype "passive"))
      (node (ref "XS2") (pin "13") (pinfunction "LED_GRN-_13") (pintype "passive"))
      (node (ref "XS4") (pin "13") (pinfunction "LED_GRN-_13") (pintype "passive"))
      (node (ref "ZQ1") (pin "2") (pinfunction "GND_2") (pintype "passive"))
      (node (ref "ZQ1") (pin "4") (pinfunction "GND_4") (pintype "passive"))
    )
    (net (code "48") (name "GND_ETH") (class "Default")
      (node (ref "C31") (pin "2") (pinfunction "2_2") (pintype "passive"))
      (node (ref "R31") (pin "2") (pinfunction "2_2") (pintype "passive"))
      (node (ref "XS1") (pin "0") (pinfunction "Корпус_0") (pintype "passive"))
      (node (ref "XS2") (pin "0") (pinfunction "Корпус_0") (pintype "passive"))
      (node (ref "XS3") (pin "0") (pinfunction "Корпус_0") (pintype "passive"))
      (node (ref "XS4") (pin "0") (pinfunction "Корпус_0") (pintype "passive"))
    )
    (net (code "49") (name "Net-(DD1-GPIO00{slash}E2_CRS{slash}M2M_CRS)") (class "Default")
      (node (ref "DD1") (pin "40") (pinfunction "GPIO00/E2_CRS/M2M_CRS_40") (pintype "bidirectional"))
      (node (ref "R3") (pin "1") (pinfunction "1_1") (pintype "passive"))
    )
    (net (code "50") (name "Net-(DD1-GPIO06{slash}E2_DOCLK{slash}RG2_TXCLK_{slash}M2M_TXCLK{slash}M2P_RXCLK)") (class "Default")
      (node (ref "DD1") (pin "46") (pinfunction "GPIO06/E2_DOCLK/RG2_TXCLK_/M2M_TXCLK/M2P_RXCLK_46") (pintype "bidirectional"))
      (node (ref "R4") (pin "1") (pinfunction "1_1") (pintype "passive"))
    )
    (net (code "51") (name "Net-(DD1-GPIO07{slash}E2_DICLK{slash}RG2_RXCLK{slash}_M2M_RXCLK{slash}M2P_TXCLK)") (class "Default")
      (node (ref "DD1") (pin "47") (pinfunction "GPIO07/E2_DICLK/RG2_RXCLK/_M2M_RXCLK/M2P_TXCLK_47") (pintype "bidirectional"))
      (node (ref "R14") (pin "2") (pinfunction "2_2") (pintype "passive"))
    )
    (net (code "52") (name "Net-(DD1-GPIO08{slash}E2_DIDV{slash}RG2_RXCTL_{slash}M2M_RXDV{slash}M2P_TXEN)") (class "Default")
      (node (ref "DD1") (pin "48") (pinfunction "GPIO08/E2_DIDV/RG2_RXCTL_/M2M_RXDV/M2P_TXEN_48") (pintype "bidirectional"))
      (node (ref "R13") (pin "2") (pinfunction "2_2") (pintype "passive"))
    )
    (net (code "53") (name "Net-(DD1-GPIO09{slash}E2_DI0{slash}RG2_RXD0_{slash}M2M_RXD0{slash}M2P_TXD0)") (class "Default")
      (node (ref "DD1") (pin "49") (pinfunction "GPIO09/E2_DI0/RG2_RXD0_/M2M_RXD0/M2P_TXD0_49") (pintype "bidirectional"))
      (node (ref "R12") (pin "2") (pinfunction "2_2") (pintype "passive"))
    )
    (net (code "54") (name "Net-(DD1-GPIO10{slash}E2_DI1{slash}RG2_RXD1_{slash}M2M_RXD1{slash}M2P_TXD1)") (class "Default")
      (node (ref "DD1") (pin "50") (pinfunction "GPIO10/E2_DI1/RG2_RXD1_/M2M_RXD1/M2P_TXD1_50") (pintype "bidirectional"))
      (node (ref "R11") (pin "2") (pinfunction "2_2") (pintype "passive"))
    )
    (net (code "55") (name "Net-(DD1-GPIO11{slash}E2_DI2{slash}RG2_RXD2{slash}M2M__RXD2{slash}M2P_TXD2)") (class "Default")
      (node (ref "DD1") (pin "51") (pinfunction "GPIO11/E2_DI2/RG2_RXD2/M2M__RXD2/M2P_TXD2_51") (pintype "bidirectional"))
      (node (ref "R10") (pin "2") (pinfunction "2_2") (pintype "passive"))
    )
    (net (code "56") (name "Net-(DD1-GPIO12{slash}E2_DI3{slash}RG2_RXD3{slash}M2M__RXD3{slash}M2P_TXD3)") (class "Default")
      (node (ref "DD1") (pin "52") (pinfunction "GPIO12/E2_DI3/RG2_RXD3/M2M__RXD3/M2P_TXD3_52") (pintype "bidirectional"))
      (node (ref "R9") (pin "2") (pinfunction "2_2") (pintype "passive"))
    )
    (net (code "57") (name "Net-(DD1-GPIO13{slash}E1_CRS{slash}M1M_CRS)") (class "Default")
      (node (ref "DD1") (pin "56") (pinfunction "GPIO13/E1_CRS/M1M_CRS_56") (pintype "bidirectional"))
      (node (ref "R8") (pin "2") (pinfunction "2_2") (pintype "passive"))
    )
    (net (code "58") (name "Net-(DD1-GPIO24{slash}E1_DOCLK{slash}RG1_TXCLK_{slash}M1M_TXCLK{slash}M1P_RXCLK)") (class "Default")
      (node (ref "DD1") (pin "62") (pinfunction "GPIO24/E1_DOCLK/RG1_TXCLK_/M1M_TXCLK/M1P_RXCLK_62") (pintype "bidirectional"))
      (node (ref "R7") (pin "2") (pinfunction "2_2") (pintype "passive"))
    )
    (net (code "59") (name "Net-(DD1-GPIO28{slash}E1_DICLK{slash}RG1_RXCLK_{slash}M1M_RXCLK{slash}M1P_TXCLK)") (class "Default")
      (node (ref "DD1") (pin "63") (pinfunction "GPIO28/E1_DICLK/RG1_RXCLK_/M1M_RXCLK/M1P_TXCLK_63") (pintype "bidirectional"))
      (node (ref "R6") (pin "2") (pinfunction "2_2") (pintype "passive"))
    )
    (net (code "60") (name "Net-(DD1-GPIO29{slash}E1_DIDV{slash}RG1_RXCTL_{slash}M1M_RXDV{slash}M1P_TXEN)") (class "Default")
      (node (ref "DD1") (pin "64") (pinfunction "GPIO29/E1_DIDV/RG1_RXCTL_/M1M_RXDV/M1P_TXEN_64") (pintype "bidirectional"))
      (node (ref "R5") (pin "2") (pinfunction "2_2") (pintype "passive"))
    )
    (net (code "61") (name "Net-(DD1-GPIO30{slash}E1_DI0{slash}RG1_RXD0_{slash}M1M_RXD0{slash}M1P_TXD0)") (class "Default")
      (node (ref "DD1") (pin "65") (pinfunction "GPIO30/E1_DI0/RG1_RXD0_/M1M_RXD0/M1P_TXD0_65") (pintype "bidirectional"))
      (node (ref "R15") (pin "2") (pinfunction "2_2") (pintype "passive"))
    )
    (net (code "62") (name "Net-(DD1-GPIO31{slash}E1_DI1{slash}RG1_RXD1_{slash}M1M_RXD1{slash}M1P_TXD1)") (class "Default")
      (node (ref "DD1") (pin "66") (pinfunction "GPIO31/E1_DI1/RG1_RXD1_/M1M_RXD1/M1P_TXD1_66") (pintype "bidirectional"))
      (node (ref "R16") (pin "2") (pinfunction "2_2") (pintype "passive"))
    )
    (net (code "63") (name "Net-(DD1-GPIO32{slash}E1_DI2{slash}RG1_RXD2_{slash}M1M_RXD2{slash}M1P_TXD2)") (class "Default")
      (node (ref "DD1") (pin "67") (pinfunction "GPIO32/E1_DI2/RG1_RXD2_/M1M_RXD2/M1P_TXD2_67") (pintype "bidirectional"))
      (node (ref "R17") (pin "2") (pinfunction "2_2") (pintype "passive"))
    )
    (net (code "64") (name "Net-(DD1-GPIO33{slash}E1_DI3{slash}RG1_RXD3_{slash}M1M_RXD3{slash}M1P_TXD3)") (class "Default")
      (node (ref "DD1") (pin "68") (pinfunction "GPIO33/E1_DI3/RG1_RXD3_/M1M_RXD3/M1P_TXD3_68") (pintype "bidirectional"))
      (node (ref "R18") (pin "2") (pinfunction "2_2") (pintype "passive"))
    )
    (net (code "65") (name "Net-(DD1-GPIO58{slash}DIS_LPD)") (class "Default")
      (node (ref "DD1") (pin "20") (pinfunction "GPIO58/DIS_LPD_20") (pintype "bidirectional"))
      (node (ref "R2") (pin "2") (pinfunction "2_2") (pintype "passive"))
    )
    (net (code "66") (name "Net-(DD1-GP_O38{slash}P4LED2{slash}DIS_SPIS)") (class "Default")
      (node (ref "DD1") (pin "72") (pinfunction "GP_O38/P4LED2/DIS_SPIS_72") (pintype "bidirectional"))
      (node (ref "R34") (pin "1") (pinfunction "1_1") (pintype "passive"))
    )
    (net (code "67") (name "Net-(DD1-GP_O39{slash}P4LED0{slash}EEPROM_MOD)") (class "Default")
      (node (ref "DD1") (pin "73") (pinfunction "GP_O39/P4LED0/EEPROM_MOD_73") (pintype "bidirectional"))
      (node (ref "R33") (pin "1") (pinfunction "1_1") (pintype "passive"))
    )
    (net (code "68") (name "Net-(DD1-MDIREF)") (class "Default")
      (node (ref "DD1") (pin "13") (pinfunction "MDIREF_13") (pintype "bidirectional"))
      (node (ref "R1") (pin "2") (pinfunction "2_2") (pintype "passive"))
    )
    (net (code "69") (name "Net-(DD1-XTALI)") (class "Default")
      (node (ref "C23") (pin "1") (pinfunction "1_1") (pintype "passive"))
      (node (ref "DD1") (pin "90") (pinfunction "XTALI_90") (pintype "bidirectional"))
      (node (ref "ZQ1") (pin "3") (pinfunction "3_3") (pintype "passive"))
    )
    (net (code "70") (name "Net-(DD1-XTALO)") (class "Default")
      (node (ref "C20") (pin "2") (pinfunction "2_2") (pintype "passive"))
      (node (ref "DD1") (pin "89") (pinfunction "XTALO_89") (pintype "bidirectional"))
      (node (ref "ZQ1") (pin "1") (pinfunction "1_1") (pintype "passive"))
    )
    (net (code "71") (name "Net-(DD1-nRESET)") (class "Default")
      (node (ref "C25") (pin "2") (pinfunction "2_2") (pintype "passive"))
      (node (ref "DD1") (pin "91") (pinfunction "nRESET_91") (pintype "bidirectional"))
      (node (ref "R19") (pin "1") (pinfunction "1_1") (pintype "passive"))
      (node (ref "S1") (pin "1") (pinfunction "1_1") (pintype "passive"))
    )
    (net (code "72") (name "Net-(XS1-LED_GRN+)") (class "Default")
      (node (ref "R39") (pin "2") (pinfunction "2_2") (pintype "passive"))
      (node (ref "XS1") (pin "14") (pinfunction "LED_GRN+_14") (pintype "passive"))
    )
    (net (code "73") (name "Net-(XS1-LED_YELLOW-)") (class "Default")
      (node (ref "R35") (pin "2") (pinfunction "2_2") (pintype "passive"))
      (node (ref "XS1") (pin "16") (pinfunction "LED_YELLOW-_16") (pintype "passive"))
    )
    (net (code "74") (name "Net-(XS1-MDCT1)") (class "Default")
      (node (ref "C32") (pin "1") (pinfunction "1_1") (pintype "passive"))
      (node (ref "XS1") (pin "1") (pinfunction "MDCT3_1") (pintype "passive"))
      (node (ref "XS1") (pin "12") (pinfunction "MDCT1_12") (pintype "passive"))
      (node (ref "XS1") (pin "6") (pinfunction "MDCT2_6") (pintype "passive"))
      (node (ref "XS1") (pin "7") (pinfunction "MDCT4_7") (pintype "passive"))
    )
    (net (code "75") (name "Net-(XS2-LED_GRN+)") (class "Default")
      (node (ref "R40") (pin "2") (pinfunction "2_2") (pintype "passive"))
      (node (ref "XS2") (pin "14") (pinfunction "LED_GRN+_14") (pintype "passive"))
    )
    (net (code "76") (name "Net-(XS2-LED_YELLOW-)") (class "Default")
      (node (ref "R36") (pin "2") (pinfunction "2_2") (pintype "passive"))
      (node (ref "XS2") (pin "16") (pinfunction "LED_YELLOW-_16") (pintype "passive"))
    )
    (net (code "77") (name "Net-(XS2-MDCT1)") (class "Default")
      (node (ref "C33") (pin "1") (pinfunction "1_1") (pintype "passive"))
      (node (ref "XS2") (pin "1") (pinfunction "MDCT3_1") (pintype "passive"))
      (node (ref "XS2") (pin "12") (pinfunction "MDCT1_12") (pintype "passive"))
      (node (ref "XS2") (pin "6") (pinfunction "MDCT2_6") (pintype "passive"))
      (node (ref "XS2") (pin "7") (pinfunction "MDCT4_7") (pintype "passive"))
    )
    (net (code "78") (name "Net-(XS3-LED_GRN+)") (class "Default")
      (node (ref "R41") (pin "2") (pinfunction "2_2") (pintype "passive"))
      (node (ref "XS3") (pin "14") (pinfunction "LED_GRN+_14") (pintype "passive"))
    )
    (net (code "79") (name "Net-(XS3-LED_YELLOW-)") (class "Default")
      (node (ref "R37") (pin "2") (pinfunction "2_2") (pintype "passive"))
      (node (ref "XS3") (pin "16") (pinfunction "LED_YELLOW-_16") (pintype "passive"))
    )
    (net (code "80") (name "Net-(XS3-MDCT1)") (class "Default")
      (node (ref "C34") (pin "1") (pinfunction "1_1") (pintype "passive"))
      (node (ref "XS3") (pin "1") (pinfunction "MDCT3_1") (pintype "passive"))
      (node (ref "XS3") (pin "12") (pinfunction "MDCT1_12") (pintype "passive"))
      (node (ref "XS3") (pin "6") (pinfunction "MDCT2_6") (pintype "passive"))
      (node (ref "XS3") (pin "7") (pinfunction "MDCT4_7") (pintype "passive"))
    )
    (net (code "81") (name "Net-(XS4-LED_GRN+)") (class "Default")
      (node (ref "R42") (pin "2") (pinfunction "2_2") (pintype "passive"))
      (node (ref "XS4") (pin "14") (pinfunction "LED_GRN+_14") (pintype "passive"))
    )
    (net (code "82") (name "Net-(XS4-LED_YELLOW-)") (class "Default")
      (node (ref "R38") (pin "2") (pinfunction "2_2") (pintype "passive"))
      (node (ref "XS4") (pin "16") (pinfunction "LED_YELLOW-_16") (pintype "passive"))
    )
    (net (code "83") (name "Net-(XS4-MDCT1)") (class "Default")
      (node (ref "C35") (pin "1") (pinfunction "1_1") (pintype "passive"))
      (node (ref "XS4") (pin "1") (pinfunction "MDCT3_1") (pintype "passive"))
      (node (ref "XS4") (pin "12") (pinfunction "MDCT1_12") (pintype "passive"))
      (node (ref "XS4") (pin "6") (pinfunction "MDCT2_6") (pintype "passive"))
      (node (ref "XS4") (pin "7") (pinfunction "MDCT4_7") (pintype "passive"))
    )
    (net (code "84") (name "unconnected-(DD1-ATESTCK-Pad117)") (class "Default")
      (node (ref "DD1") (pin "117") (pinfunction "ATESTCK_117") (pintype "bidirectional+no_connect"))
    )
    (net (code "85") (name "unconnected-(DD1-GPIO01{slash}E2_DO3{slash}RG2_TXD3_{slash}M2M_TXD3{slash}M2P_RXD3-Pad41)") (class "Default")
      (node (ref "DD1") (pin "41") (pinfunction "GPIO01/E2_DO3/RG2_TXD3_/M2M_TXD3/M2P_RXD3_41") (pintype "bidirectional+no_connect"))
    )
    (net (code "86") (name "unconnected-(DD1-GPIO02{slash}E2_DO2{slash}RG2_TXD2_{slash}M2M_TXD2{slash}M2P_RXD2-Pad42)") (class "Default")
      (node (ref "DD1") (pin "42") (pinfunction "GPIO02/E2_DO2/RG2_TXD2_/M2M_TXD2/M2P_RXD2_42") (pintype "bidirectional+no_connect"))
    )
    (net (code "87") (name "unconnected-(DD1-GPIO03{slash}E2_DO1{slash}RG2_TXD1_{slash}M2M_TXD1{slash}M2P_RXD-Pad43)") (class "Default")
      (node (ref "DD1") (pin "43") (pinfunction "GPIO03/E2_DO1/RG2_TXD1_/M2M_TXD1/M2P_RXD_43") (pintype "bidirectional+no_connect"))
    )
    (net (code "88") (name "unconnected-(DD1-GPIO04{slash}E2_DO0{slash}RG2_TXD0_{slash}M2M_TXD0{slash}M2P_RXD0-Pad44)") (class "Default")
      (node (ref "DD1") (pin "44") (pinfunction "GPIO04/E2_DO0/RG2_TXD0_/M2M_TXD0/M2P_RXD0_44") (pintype "bidirectional+no_connect"))
    )
    (net (code "89") (name "unconnected-(DD1-GPIO05{slash}E2_DOEN{slash}RG2_TXCTL{slash}_M2M_TXEN{slash}M2P_RXDV-Pad45)") (class "Default")
      (node (ref "DD1") (pin "45") (pinfunction "GPIO05/E2_DOEN/RG2_TXCTL/_M2M_TXEN/M2P_RXDV_45") (pintype "bidirectional+no_connect"))
    )
    (net (code "90") (name "unconnected-(DD1-GPIO19{slash}E1_DO3{slash}RG1_TXD3_{slash}M1M_TXD3{slash}M1P_RXD3-Pad57)") (class "Default")
      (node (ref "DD1") (pin "57") (pinfunction "GPIO19/E1_DO3/RG1_TXD3_/M1M_TXD3/M1P_RXD3_57") (pintype "bidirectional+no_connect"))
    )
    (net (code "91") (name "unconnected-(DD1-GPIO20{slash}E1_DO2{slash}RG1_TXD2{slash}M1_M_TXD2{slash}M1P_RXD2-Pad58)") (class "Default")
      (node (ref "DD1") (pin "58") (pinfunction "GPIO20/E1_DO2/RG1_TXD2/M1_M_TXD2/M1P_RXD2_58") (pintype "bidirectional+no_connect"))
    )
    (net (code "92") (name "unconnected-(DD1-GPIO21{slash}E1_DO1{slash}RG1_TXD1{slash}M1_M_TXD1{slash}M1P_RXD1-Pad59)") (class "Default")
      (node (ref "DD1") (pin "59") (pinfunction "GPIO21/E1_DO1/RG1_TXD1/M1_M_TXD1/M1P_RXD1_59") (pintype "bidirectional+no_connect"))
    )
    (net (code "93") (name "unconnected-(DD1-GPIO22{slash}E1_DO0{slash}RG1_TXD0{slash}M1_M_TXD0{slash}M1P_RXD0-Pad60)") (class "Default")
      (node (ref "DD1") (pin "60") (pinfunction "GPIO22/E1_DO0/RG1_TXD0/M1_M_TXD0/M1P_RXD0_60") (pintype "bidirectional+no_connect"))
    )
    (net (code "94") (name "unconnected-(DD1-GPIO23{slash}E1_DOEN{slash}RG1_TXCTL_{slash}M1M_TXEN{slash}M1P_RXDV-Pad61)") (class "Default")
      (node (ref "DD1") (pin "61") (pinfunction "GPIO23/E1_DOEN/RG1_TXCTL_/M1M_TXEN/M1P_RXDV_61") (pintype "bidirectional+no_connect"))
    )
    (net (code "95") (name "unconnected-(DD1-GPIO40{slash}P4LED1-Pad74)") (class "Default")
      (node (ref "DD1") (pin "74") (pinfunction "GPIO40/P4LED1_74") (pintype "bidirectional+no_connect"))
    )
    (net (code "96") (name "unconnected-(DD1-GPIO53{slash}SPIS_nCSI-Pad92)") (class "Default")
      (node (ref "DD1") (pin "92") (pinfunction "GPIO53/SPIS_nCSI_92") (pintype "bidirectional+no_connect"))
    )
    (net (code "97") (name "unconnected-(DD1-GPIO54{slash}SPIS_CK{slash}SCK{slash}MDC-Pad93)") (class "Default")
      (node (ref "DD1") (pin "93") (pinfunction "GPIO54/SPIS_CK/SCK/MDC_93") (pintype "bidirectional+no_connect"))
    )
    (net (code "98") (name "unconnected-(DD1-GPIO55{slash}SPIS_DI{slash}SDA{slash}MDIO-Pad94)") (class "Default")
      (node (ref "DD1") (pin "94") (pinfunction "GPIO55/SPIS_DI/SDA/MDIO_94") (pintype "bidirectional+no_connect"))
    )
    (net (code "99") (name "unconnected-(DD1-GPIO56{slash}SPIS_DO-Pad95)") (class "Default")
      (node (ref "DD1") (pin "95") (pinfunction "GPIO56/SPIS_DO_95") (pintype "bidirectional+no_connect"))
    )
    (net (code "100") (name "unconnected-(DD1-GPIO57{slash}INTERRUPT-Pad19)") (class "Default")
      (node (ref "DD1") (pin "19") (pinfunction "GPIO57/INTERRUPT_19") (pintype "bidirectional+no_connect"))
    )
    (net (code "101") (name "unconnected-(DD1-NC-Pad22)") (class "Default")
      (node (ref "DD1") (pin "22") (pinfunction "NC_22") (pintype "bidirectional+no_connect"))
    )
    (net (code "102") (name "unconnected-(DD1-NC-Pad38)") (class "Default")
      (node (ref "DD1") (pin "38") (pinfunction "NC_38") (pintype "bidirectional+no_connect"))
    )
    (net (code "103") (name "unconnected-(DD1-NC-Pad87)") (class "Default")
      (node (ref "DD1") (pin "87") (pinfunction "NC_87") (pintype "bidirectional+no_connect"))
    )
    (net (code "104") (name "unconnected-(DD1-P4MDIAN-Pad25)") (class "Default")
      (node (ref "DD1") (pin "25") (pinfunction "P4MDIAN_25") (pintype "bidirectional+no_connect"))
    )
    (net (code "105") (name "unconnected-(DD1-P4MDIAP-Pad24)") (class "Default")
      (node (ref "DD1") (pin "24") (pinfunction "P4MDIAP_24") (pintype "bidirectional+no_connect"))
    )
    (net (code "106") (name "unconnected-(DD1-P4MDIBN-Pad27)") (class "Default")
      (node (ref "DD1") (pin "27") (pinfunction "P4MDIBN_27") (pintype "bidirectional+no_connect"))
    )
    (net (code "107") (name "unconnected-(DD1-P4MDIBP-Pad26)") (class "Default")
      (node (ref "DD1") (pin "26") (pinfunction "P4MDIBP_26") (pintype "bidirectional+no_connect"))
    )
    (net (code "108") (name "unconnected-(DD1-P4MDICN-Pad30)") (class "Default")
      (node (ref "DD1") (pin "30") (pinfunction "P4MDICN_30") (pintype "bidirectional+no_connect"))
    )
    (net (code "109") (name "unconnected-(DD1-P4MDICP-Pad29)") (class "Default")
      (node (ref "DD1") (pin "29") (pinfunction "P4MDICP_29") (pintype "bidirectional+no_connect"))
    )
    (net (code "110") (name "unconnected-(DD1-P4MDIDN-Pad32)") (class "Default")
      (node (ref "DD1") (pin "32") (pinfunction "P4MDIDN_32") (pintype "bidirectional+no_connect"))
    )
    (net (code "111") (name "unconnected-(DD1-P4MDIDP-Pad31)") (class "Default")
      (node (ref "DD1") (pin "31") (pinfunction "P4MDIDP_31") (pintype "bidirectional+no_connect"))
    )
    (net (code "112") (name "unconnected-(DD1-RESERVED-Pad35)") (class "Default")
      (node (ref "DD1") (pin "35") (pinfunction "RESERVED_35") (pintype "bidirectional+no_connect"))
    )
    (net (code "113") (name "unconnected-(DD1-RESERVED-Pad37)") (class "Default")
      (node (ref "DD1") (pin "37") (pinfunction "RESERVED_37") (pintype "bidirectional+no_connect"))
    )
    (net (code "114") (name "unconnected-(DD1-RTT1-Pad15)") (class "Default")
      (node (ref "DD1") (pin "15") (pinfunction "RTT1_15") (pintype "bidirectional+no_connect"))
    )
    (net (code "115") (name "unconnected-(DD1-RTT2-Pad16)") (class "Default")
      (node (ref "DD1") (pin "16") (pinfunction "RTT2_16") (pintype "bidirectional+no_connect"))
    )
  )
)
